# M8650D_eco.net
KiCad netlist of a schematic drawn in EAGLE
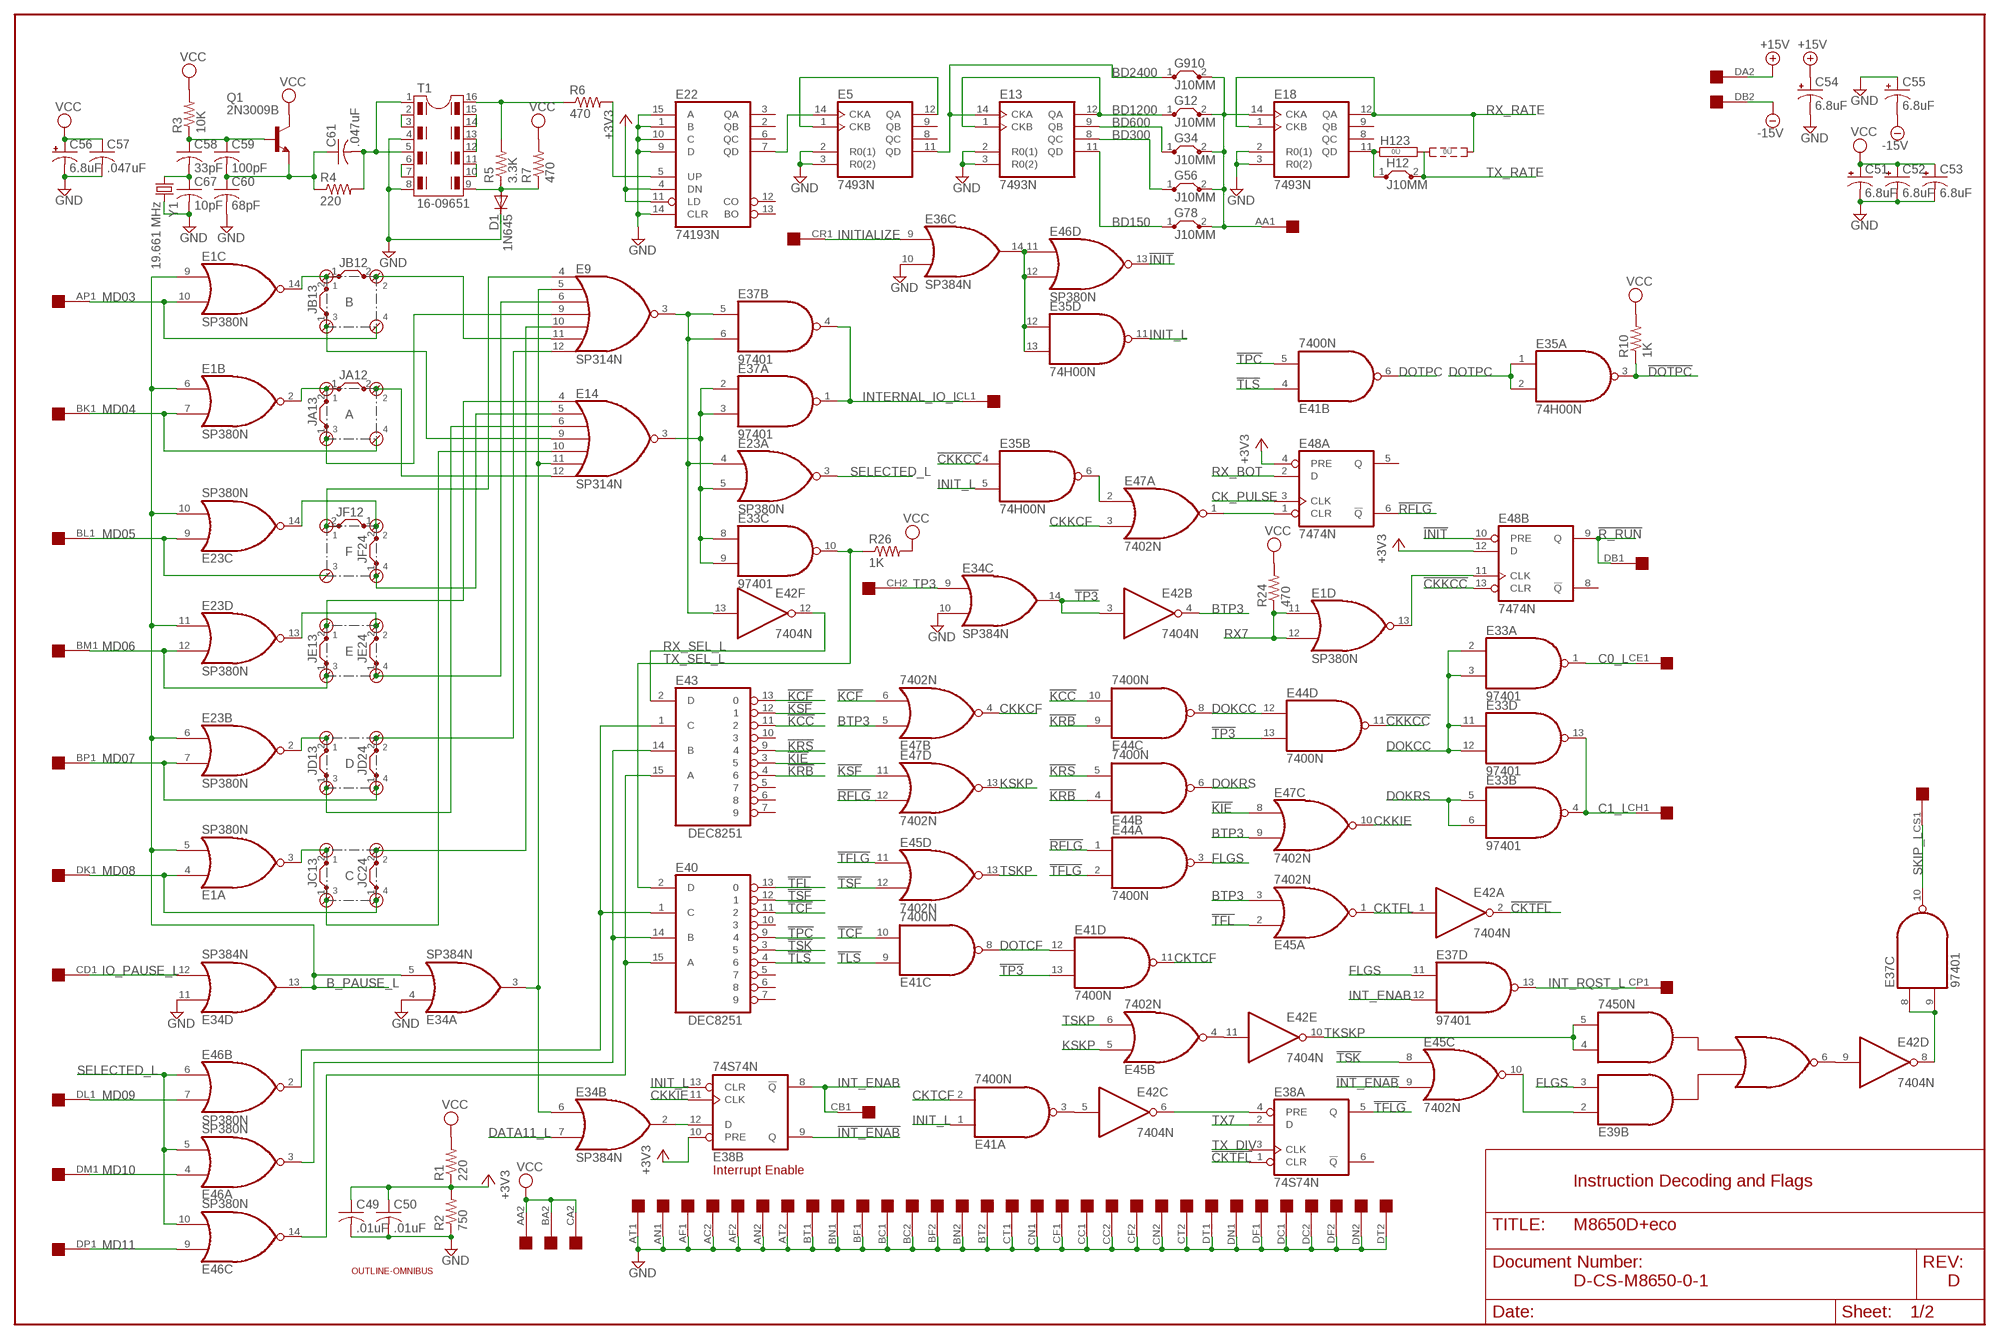
[diagram p0: schematic, sheet 1]
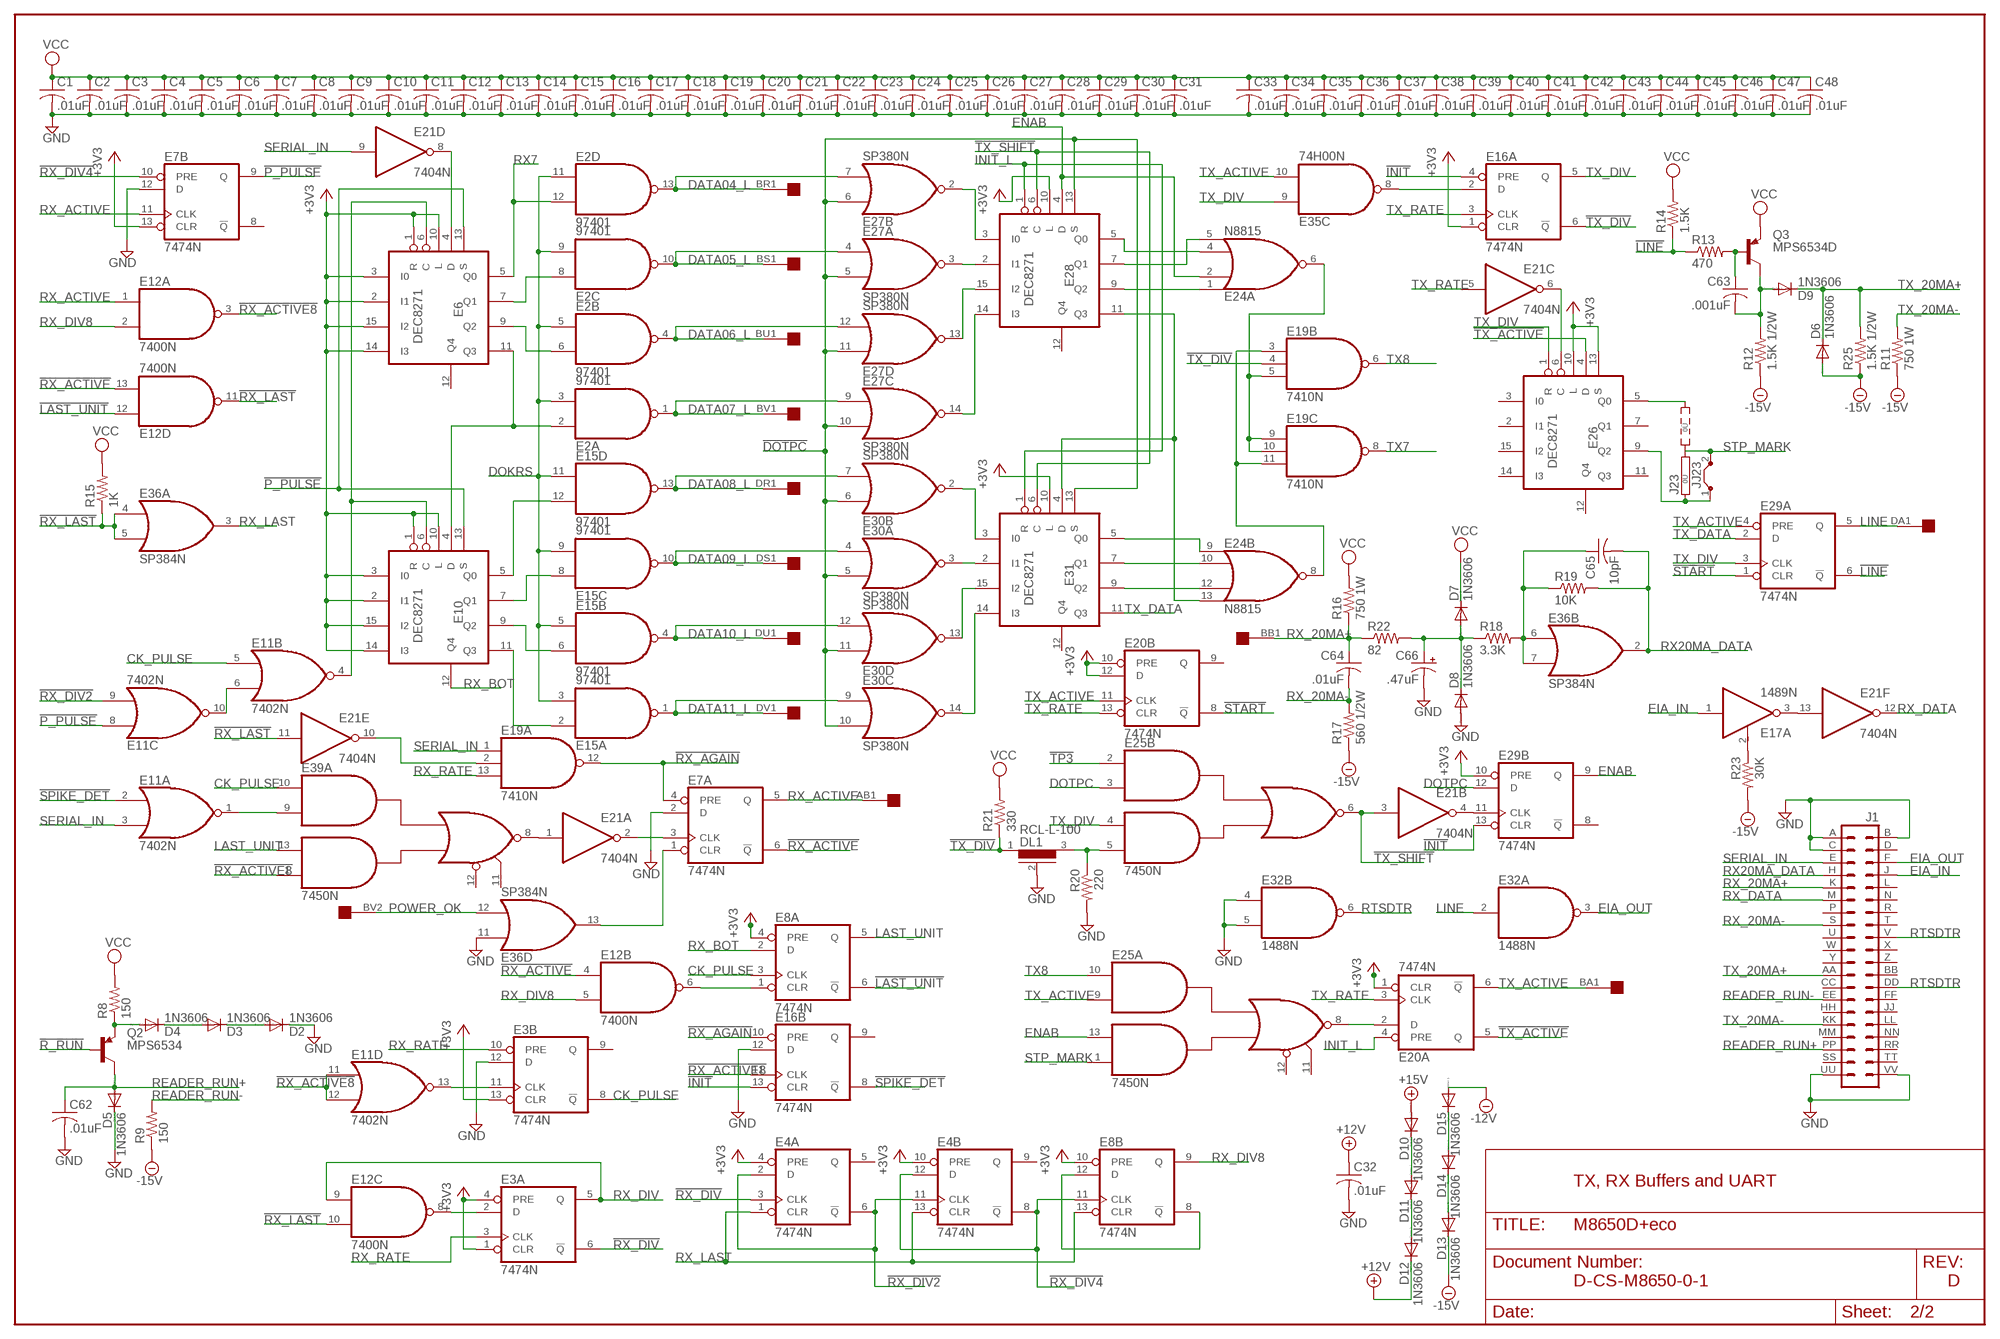
[diagram p1: schematic, sheet 2]

(export (version "E")
  (design (tool "Eeschema 10.0.6"))
  (components
    (comp (ref "A")
      (value "JUMPER4")
      (footprint "eagle-import:JUMPER4")
      (libsource (lib "eagle-import") (part "JUMPER4"))
    )
    (comp (ref "B")
      (value "JUMPER4")
      (footprint "eagle-import:JUMPER4")
      (libsource (lib "eagle-import") (part "JUMPER4"))
    )
    (comp (ref "C")
      (value "JUMPER4")
      (footprint "eagle-import:JUMPER4")
      (libsource (lib "eagle-import") (part "JUMPER4"))
    )
    (comp (ref "C49")
      (value ".01uF")
      (footprint "eagle-import:C050-025X075")
      (libsource (lib "eagle-import") (part "C-US050-025X075"))
    )
    (comp (ref "C50")
      (value ".01uF")
      (footprint "eagle-import:C050-025X075")
      (libsource (lib "eagle-import") (part "C-US050-025X075"))
    )
    (comp (ref "C51")
      (value "6.8uF")
      (footprint "eagle-import:E12-8")
      (libsource (lib "eagle-import") (part "CPOL-USE20-8AXIAL"))
    )
    (comp (ref "C52")
      (value "6.8uF")
      (footprint "eagle-import:E12-8")
      (libsource (lib "eagle-import") (part "CPOL-USE20-8AXIAL"))
    )
    (comp (ref "C53")
      (value "6.8uF")
      (footprint "eagle-import:E12-8")
      (libsource (lib "eagle-import") (part "CPOL-USE20-8AXIAL"))
    )
    (comp (ref "C54")
      (value "6.8uF")
      (footprint "eagle-import:E12-8")
      (libsource (lib "eagle-import") (part "CPOL-USE20-8AXIAL"))
    )
    (comp (ref "C55")
      (value "6.8uF")
      (footprint "eagle-import:E12-8")
      (libsource (lib "eagle-import") (part "CPOL-USE20-8AXIAL"))
    )
    (comp (ref "C56")
      (value "6.8uF")
      (footprint "eagle-import:E12-8")
      (libsource (lib "eagle-import") (part "CPOL-USE20-8AXIAL"))
    )
    (comp (ref "C57")
      (value ".047uF")
      (footprint "eagle-import:C050-025X075")
      (libsource (lib "eagle-import") (part "C-US050-025X075"))
    )
    (comp (ref "C58")
      (value "33pF")
      (footprint "eagle-import:C050-025X075")
      (libsource (lib "eagle-import") (part "C-US050-025X075"))
    )
    (comp (ref "C59")
      (value "100pF")
      (footprint "eagle-import:C050-025X075")
      (libsource (lib "eagle-import") (part "C-US050-025X075"))
    )
    (comp (ref "C60")
      (value "68pF")
      (footprint "eagle-import:C050-025X075")
      (libsource (lib "eagle-import") (part "C-US050-025X075"))
    )
    (comp (ref "C61")
      (value ".047uF")
      (footprint "eagle-import:C050-025X075")
      (libsource (lib "eagle-import") (part "C-US050-025X075"))
    )
    (comp (ref "C67")
      (value "10pF")
      (footprint "eagle-import:C050-025X075")
      (libsource (lib "eagle-import") (part "C-US050-025X075"))
    )
    (comp (ref "D")
      (value "JUMPER4")
      (footprint "eagle-import:JUMPER4")
      (libsource (lib "eagle-import") (part "JUMPER4"))
    )
    (comp (ref "D1")
      (value "1N645")
      (footprint "eagle-import:DO35-10")
      (libsource (lib "eagle-import") (part "DIODE-DO35-10"))
    )
    (comp (ref "E")
      (value "JUMPER4")
      (footprint "eagle-import:JUMPER4")
      (libsource (lib "eagle-import") (part "JUMPER4"))
    )
    (comp (ref "E1")
      (value "SP380N")
      (footprint "eagle-import:DIL14")
      (libsource (lib "eagle-import") (part "SP380N"))
    )
    (comp (ref "E5")
      (value "7493N")
      (footprint "eagle-import:DIL14")
      (libsource (lib "eagle-import") (part "7493NLS"))
    )
    (comp (ref "E9")
      (value "SP314N")
      (footprint "eagle-import:DIL14")
      (libsource (lib "eagle-import") (part "SP314N"))
    )
    (comp (ref "E13")
      (value "7493N")
      (footprint "eagle-import:DIL14")
      (libsource (lib "eagle-import") (part "7493NLS"))
    )
    (comp (ref "E14")
      (value "SP314N")
      (footprint "eagle-import:DIL14")
      (libsource (lib "eagle-import") (part "SP314N"))
    )
    (comp (ref "E18")
      (value "7493N")
      (footprint "eagle-import:DIL14")
      (libsource (lib "eagle-import") (part "7493NLS"))
    )
    (comp (ref "E22")
      (value "74193N")
      (footprint "eagle-import:DIL16")
      (libsource (lib "eagle-import") (part "74193N"))
    )
    (comp (ref "E23")
      (value "SP380N")
      (footprint "eagle-import:DIL14")
      (libsource (lib "eagle-import") (part "SP380N"))
    )
    (comp (ref "E33")
      (value "97401")
      (footprint "eagle-import:DIL14")
      (libsource (lib "eagle-import") (part "7401NLS"))
    )
    (comp (ref "E34")
      (value "SP384N")
      (footprint "eagle-import:DIL14")
      (libsource (lib "eagle-import") (part "SP384N"))
    )
    (comp (ref "E35")
      (value "74H00N")
      (footprint "eagle-import:DIL14")
      (libsource (lib "eagle-import") (part "7400N"))
    )
    (comp (ref "E36")
      (value "SP384N")
      (footprint "eagle-import:DIL14")
      (libsource (lib "eagle-import") (part "SP384N"))
    )
    (comp (ref "E37")
      (value "97401")
      (footprint "eagle-import:DIL14")
      (libsource (lib "eagle-import") (part "7401NLS"))
    )
    (comp (ref "E38")
      (value "74S74N")
      (footprint "eagle-import:DIL14")
      (libsource (lib "eagle-import") (part "7474NS"))
    )
    (comp (ref "E39")
      (value "7450N")
      (footprint "eagle-import:DIL14")
      (libsource (lib "eagle-import") (part "7450N"))
    )
    (comp (ref "E40")
      (value "DEC8251")
      (footprint "eagle-import:DIL16")
      (libsource (lib "eagle-import") (part "DEC8251"))
    )
    (comp (ref "E41")
      (value "7400N")
      (footprint "eagle-import:DIL14")
      (libsource (lib "eagle-import") (part "7400N"))
    )
    (comp (ref "E42")
      (value "7404N")
      (footprint "eagle-import:DIL14")
      (libsource (lib "eagle-import") (part "7404N"))
    )
    (comp (ref "E43")
      (value "DEC8251")
      (footprint "eagle-import:DIL16")
      (libsource (lib "eagle-import") (part "DEC8251"))
    )
    (comp (ref "E44")
      (value "7400N")
      (footprint "eagle-import:DIL14")
      (libsource (lib "eagle-import") (part "7400N"))
    )
    (comp (ref "E45")
      (value "7402N")
      (footprint "eagle-import:DIL14")
      (libsource (lib "eagle-import") (part "7402N"))
    )
    (comp (ref "E46")
      (value "SP380N")
      (footprint "eagle-import:DIL14")
      (libsource (lib "eagle-import") (part "SP380N"))
    )
    (comp (ref "E47")
      (value "7402N")
      (footprint "eagle-import:DIL14")
      (libsource (lib "eagle-import") (part "7402N"))
    )
    (comp (ref "E48")
      (value "7474N")
      (footprint "eagle-import:DIL14")
      (libsource (lib "eagle-import") (part "7474NS"))
    )
    (comp (ref "F")
      (value "JUMPER4")
      (footprint "eagle-import:JUMPER4")
      (libsource (lib "eagle-import") (part "JUMPER4"))
    )
    (comp (ref "G12")
      (value "J10MM")
      (footprint "eagle-import:10")
      (libsource (lib "eagle-import") (part "J10MM"))
    )
    (comp (ref "G34")
      (value "J10MM")
      (footprint "eagle-import:10")
      (libsource (lib "eagle-import") (part "J10MM"))
    )
    (comp (ref "G56")
      (value "J10MM")
      (footprint "eagle-import:10")
      (libsource (lib "eagle-import") (part "J10MM"))
    )
    (comp (ref "G78")
      (value "J10MM")
      (footprint "eagle-import:10")
      (libsource (lib "eagle-import") (part "J10MM"))
    )
    (comp (ref "G910")
      (value "J10MM")
      (footprint "eagle-import:10")
      (libsource (lib "eagle-import") (part "J10MM"))
    )
    (comp (ref "H12")
      (value "J10MM")
      (footprint "eagle-import:10")
      (libsource (lib "eagle-import") (part "J10MM"))
    )
    (comp (ref "H123")
      (value "0R2")
      (footprint "eagle-import:0R2_10")
      (libsource (lib "eagle-import") (part "0R2"))
    )
    (comp (ref "JA12")
      (value "J10MM")
      (footprint "eagle-import:10")
      (libsource (lib "eagle-import") (part "J10MM"))
    )
    (comp (ref "JA13")
      (value "J10MM")
      (footprint "eagle-import:10")
      (libsource (lib "eagle-import") (part "J10MM"))
    )
    (comp (ref "JB12")
      (value "J10MM")
      (footprint "eagle-import:10")
      (libsource (lib "eagle-import") (part "J10MM"))
    )
    (comp (ref "JB13")
      (value "J10MM")
      (footprint "eagle-import:10")
      (libsource (lib "eagle-import") (part "J10MM"))
    )
    (comp (ref "JC13")
      (value "J10MM")
      (footprint "eagle-import:10")
      (libsource (lib "eagle-import") (part "J10MM"))
    )
    (comp (ref "JC24")
      (value "J10MM")
      (footprint "eagle-import:10")
      (libsource (lib "eagle-import") (part "J10MM"))
    )
    (comp (ref "JD13")
      (value "J10MM")
      (footprint "eagle-import:10")
      (libsource (lib "eagle-import") (part "J10MM"))
    )
    (comp (ref "JD24")
      (value "J10MM")
      (footprint "eagle-import:10")
      (libsource (lib "eagle-import") (part "J10MM"))
    )
    (comp (ref "JE13")
      (value "J10MM")
      (footprint "eagle-import:10")
      (libsource (lib "eagle-import") (part "J10MM"))
    )
    (comp (ref "JE24")
      (value "J10MM")
      (footprint "eagle-import:10")
      (libsource (lib "eagle-import") (part "J10MM"))
    )
    (comp (ref "JF12")
      (value "J10MM")
      (footprint "eagle-import:10")
      (libsource (lib "eagle-import") (part "J10MM"))
    )
    (comp (ref "JF24")
      (value "J10MM")
      (footprint "eagle-import:10")
      (libsource (lib "eagle-import") (part "J10MM"))
    )
    (comp (ref "Q1")
      (value "2N3009B")
      (footprint "eagle-import:TO5")
      (libsource (lib "eagle-import") (part "-NPN-TO5"))
    )
    (comp (ref "R1")
      (value "220")
      (footprint "eagle-import:0207_10")
      (libsource (lib "eagle-import") (part "R-US_0207/10"))
    )
    (comp (ref "R2")
      (value "750")
      (footprint "eagle-import:0207_10")
      (libsource (lib "eagle-import") (part "R-US_0207/10"))
    )
    (comp (ref "R3")
      (value "10K")
      (footprint "eagle-import:0207_10")
      (libsource (lib "eagle-import") (part "R-US_0207/10"))
    )
    (comp (ref "R4")
      (value "220")
      (footprint "eagle-import:0207_10")
      (libsource (lib "eagle-import") (part "R-US_0207/10"))
    )
    (comp (ref "R5")
      (value "3.3K")
      (footprint "eagle-import:0207_10")
      (libsource (lib "eagle-import") (part "R-US_0207/10"))
    )
    (comp (ref "R6")
      (value "470")
      (footprint "eagle-import:0207_10")
      (libsource (lib "eagle-import") (part "R-US_0207/10"))
    )
    (comp (ref "R7")
      (value "470")
      (footprint "eagle-import:0207_10")
      (libsource (lib "eagle-import") (part "R-US_0207/10"))
    )
    (comp (ref "R10")
      (value "1K")
      (footprint "eagle-import:0207_10")
      (libsource (lib "eagle-import") (part "R-US_0207/10"))
    )
    (comp (ref "R24")
      (value "470")
      (footprint "eagle-import:0207_10")
      (libsource (lib "eagle-import") (part "R-US_0207/10"))
    )
    (comp (ref "R26")
      (value "1K")
      (footprint "eagle-import:0207_10")
      (libsource (lib "eagle-import") (part "R-US_0207/10"))
    )
    (comp (ref "T1")
      (value "16-09651")
      (footprint "eagle-import:DIL16")
      (libsource (lib "eagle-import") (part "DIL16"))
    )
    (comp (ref "U$1")
      (value "OUTLINE-OMNIBUS")
      (footprint "eagle-import:OMNIBUS")
      (libsource (lib "eagle-import") (part "OUTLINE-OMNIBUS"))
    )
    (comp (ref "U$2")
      (value "QUAD")
      (footprint "eagle-import:EDGE-CON8")
      (libsource (lib "eagle-import") (part "QUAD"))
    )
    (comp (ref "Y1")
      (value "19.661 MHz")
      (footprint "eagle-import:HC49TL-H")
      (libsource (lib "eagle-import") (part "CRYSTALHC49TL-H"))
    )
    (comp (ref "C1")
      (value ".01uF")
      (footprint "eagle-import:C050-025X075")
      (libsource (lib "eagle-import") (part "C-US050-025X075"))
    )
    (comp (ref "C2")
      (value ".01uF")
      (footprint "eagle-import:C050-025X075")
      (libsource (lib "eagle-import") (part "C-US050-025X075"))
    )
    (comp (ref "C3")
      (value ".01uF")
      (footprint "eagle-import:C050-025X075")
      (libsource (lib "eagle-import") (part "C-US050-025X075"))
    )
    (comp (ref "C4")
      (value ".01uF")
      (footprint "eagle-import:C050-025X075")
      (libsource (lib "eagle-import") (part "C-US050-025X075"))
    )
    (comp (ref "C5")
      (value ".01uF")
      (footprint "eagle-import:C050-025X075")
      (libsource (lib "eagle-import") (part "C-US050-025X075"))
    )
    (comp (ref "C6")
      (value ".01uF")
      (footprint "eagle-import:C050-025X075")
      (libsource (lib "eagle-import") (part "C-US050-025X075"))
    )
    (comp (ref "C7")
      (value ".01uF")
      (footprint "eagle-import:C050-025X075")
      (libsource (lib "eagle-import") (part "C-US050-025X075"))
    )
    (comp (ref "C8")
      (value ".01uF")
      (footprint "eagle-import:C050-025X075")
      (libsource (lib "eagle-import") (part "C-US050-025X075"))
    )
    (comp (ref "C9")
      (value ".01uF")
      (footprint "eagle-import:C050-025X075")
      (libsource (lib "eagle-import") (part "C-US050-025X075"))
    )
    (comp (ref "C10")
      (value ".01uF")
      (footprint "eagle-import:C050-025X075")
      (libsource (lib "eagle-import") (part "C-US050-025X075"))
    )
    (comp (ref "C11")
      (value ".01uF")
      (footprint "eagle-import:C050-025X075")
      (libsource (lib "eagle-import") (part "C-US050-025X075"))
    )
    (comp (ref "C12")
      (value ".01uF")
      (footprint "eagle-import:C050-025X075")
      (libsource (lib "eagle-import") (part "C-US050-025X075"))
    )
    (comp (ref "C13")
      (value ".01uF")
      (footprint "eagle-import:C050-025X075")
      (libsource (lib "eagle-import") (part "C-US050-025X075"))
    )
    (comp (ref "C14")
      (value ".01uF")
      (footprint "eagle-import:C050-025X075")
      (libsource (lib "eagle-import") (part "C-US050-025X075"))
    )
    (comp (ref "C15")
      (value ".01uF")
      (footprint "eagle-import:C050-025X075")
      (libsource (lib "eagle-import") (part "C-US050-025X075"))
    )
    (comp (ref "C16")
      (value ".01uF")
      (footprint "eagle-import:C050-025X075")
      (libsource (lib "eagle-import") (part "C-US050-025X075"))
    )
    (comp (ref "C17")
      (value ".01uF")
      (footprint "eagle-import:C050-025X075")
      (libsource (lib "eagle-import") (part "C-US050-025X075"))
    )
    (comp (ref "C18")
      (value ".01uF")
      (footprint "eagle-import:C050-025X075")
      (libsource (lib "eagle-import") (part "C-US050-025X075"))
    )
    (comp (ref "C19")
      (value ".01uF")
      (footprint "eagle-import:C050-025X075")
      (libsource (lib "eagle-import") (part "C-US050-025X075"))
    )
    (comp (ref "C20")
      (value ".01uF")
      (footprint "eagle-import:C050-025X075")
      (libsource (lib "eagle-import") (part "C-US050-025X075"))
    )
    (comp (ref "C21")
      (value ".01uF")
      (footprint "eagle-import:C050-025X075")
      (libsource (lib "eagle-import") (part "C-US050-025X075"))
    )
    (comp (ref "C22")
      (value ".01uF")
      (footprint "eagle-import:C050-025X075")
      (libsource (lib "eagle-import") (part "C-US050-025X075"))
    )
    (comp (ref "C23")
      (value ".01uF")
      (footprint "eagle-import:C050-025X075")
      (libsource (lib "eagle-import") (part "C-US050-025X075"))
    )
    (comp (ref "C24")
      (value ".01uF")
      (footprint "eagle-import:C050-025X075")
      (libsource (lib "eagle-import") (part "C-US050-025X075"))
    )
    (comp (ref "C25")
      (value ".01uF")
      (footprint "eagle-import:C050-025X075")
      (libsource (lib "eagle-import") (part "C-US050-025X075"))
    )
    (comp (ref "C26")
      (value ".01uF")
      (footprint "eagle-import:C050-025X075")
      (libsource (lib "eagle-import") (part "C-US050-025X075"))
    )
    (comp (ref "C27")
      (value ".01uF")
      (footprint "eagle-import:C050-025X075")
      (libsource (lib "eagle-import") (part "C-US050-025X075"))
    )
    (comp (ref "C28")
      (value ".01uF")
      (footprint "eagle-import:C050-025X075")
      (libsource (lib "eagle-import") (part "C-US050-025X075"))
    )
    (comp (ref "C29")
      (value ".01uF")
      (footprint "eagle-import:C050-025X075")
      (libsource (lib "eagle-import") (part "C-US050-025X075"))
    )
    (comp (ref "C30")
      (value ".01uF")
      (footprint "eagle-import:C050-025X075")
      (libsource (lib "eagle-import") (part "C-US050-025X075"))
    )
    (comp (ref "C31")
      (value ".01uF")
      (footprint "eagle-import:C050-025X075")
      (libsource (lib "eagle-import") (part "C-US050-025X075"))
    )
    (comp (ref "C32")
      (value ".01uF")
      (footprint "eagle-import:C050-025X075")
      (libsource (lib "eagle-import") (part "C-US050-025X075"))
    )
    (comp (ref "C33")
      (value ".01uF")
      (footprint "eagle-import:C050-025X075")
      (libsource (lib "eagle-import") (part "C-US050-025X075"))
    )
    (comp (ref "C34")
      (value ".01uF")
      (footprint "eagle-import:C050-025X075")
      (libsource (lib "eagle-import") (part "C-US050-025X075"))
    )
    (comp (ref "C35")
      (value ".01uF")
      (footprint "eagle-import:C050-025X075")
      (libsource (lib "eagle-import") (part "C-US050-025X075"))
    )
    (comp (ref "C36")
      (value ".01uF")
      (footprint "eagle-import:C050-025X075")
      (libsource (lib "eagle-import") (part "C-US050-025X075"))
    )
    (comp (ref "C37")
      (value ".01uF")
      (footprint "eagle-import:C050-025X075")
      (libsource (lib "eagle-import") (part "C-US050-025X075"))
    )
    (comp (ref "C38")
      (value ".01uF")
      (footprint "eagle-import:C050-025X075")
      (libsource (lib "eagle-import") (part "C-US050-025X075"))
    )
    (comp (ref "C39")
      (value ".01uF")
      (footprint "eagle-import:C050-025X075")
      (libsource (lib "eagle-import") (part "C-US050-025X075"))
    )
    (comp (ref "C40")
      (value ".01uF")
      (footprint "eagle-import:C050-025X075")
      (libsource (lib "eagle-import") (part "C-US050-025X075"))
    )
    (comp (ref "C41")
      (value ".01uF")
      (footprint "eagle-import:C050-025X075")
      (libsource (lib "eagle-import") (part "C-US050-025X075"))
    )
    (comp (ref "C42")
      (value ".01uF")
      (footprint "eagle-import:C050-025X075")
      (libsource (lib "eagle-import") (part "C-US050-025X075"))
    )
    (comp (ref "C43")
      (value ".01uF")
      (footprint "eagle-import:C050-025X075")
      (libsource (lib "eagle-import") (part "C-US050-025X075"))
    )
    (comp (ref "C44")
      (value ".01uF")
      (footprint "eagle-import:C050-025X075")
      (libsource (lib "eagle-import") (part "C-US050-025X075"))
    )
    (comp (ref "C45")
      (value ".01uF")
      (footprint "eagle-import:C050-025X075")
      (libsource (lib "eagle-import") (part "C-US050-025X075"))
    )
    (comp (ref "C46")
      (value ".01uF")
      (footprint "eagle-import:C050-025X075")
      (libsource (lib "eagle-import") (part "C-US050-025X075"))
    )
    (comp (ref "C47")
      (value ".01uF")
      (footprint "eagle-import:C050-025X075")
      (libsource (lib "eagle-import") (part "C-US050-025X075"))
    )
    (comp (ref "C48")
      (value ".01uF")
      (footprint "eagle-import:C050-025X075")
      (libsource (lib "eagle-import") (part "C-US050-025X075"))
    )
    (comp (ref "C62")
      (value ".01uF")
      (footprint "eagle-import:C050-025X075")
      (libsource (lib "eagle-import") (part "C-US050-025X075"))
    )
    (comp (ref "C63")
      (value ".001uF")
      (footprint "eagle-import:C050-025X075")
      (libsource (lib "eagle-import") (part "C-US050-025X075"))
    )
    (comp (ref "C64")
      (value ".01uF")
      (footprint "eagle-import:C050-025X075")
      (libsource (lib "eagle-import") (part "C-US050-025X075"))
    )
    (comp (ref "C65")
      (value "10pF")
      (footprint "eagle-import:C050-025X075")
      (libsource (lib "eagle-import") (part "C-US050-025X075"))
    )
    (comp (ref "C66")
      (value ".47uF")
      (footprint "eagle-import:E15-5")
      (libsource (lib "eagle-import") (part "CPOL-USE15-5AXIAL"))
    )
    (comp (ref "D2")
      (value "1N3606")
      (footprint "eagle-import:DO35-10")
      (libsource (lib "eagle-import") (part "DIODE-DO35-10"))
    )
    (comp (ref "D3")
      (value "1N3606")
      (footprint "eagle-import:DO35-10")
      (libsource (lib "eagle-import") (part "DIODE-DO35-10"))
    )
    (comp (ref "D4")
      (value "1N3606")
      (footprint "eagle-import:DO35-10")
      (libsource (lib "eagle-import") (part "DIODE-DO35-10"))
    )
    (comp (ref "D5")
      (value "1N3606")
      (footprint "eagle-import:DO35-10")
      (libsource (lib "eagle-import") (part "DIODE-DO35-10"))
    )
    (comp (ref "D6")
      (value "1N3606")
      (footprint "eagle-import:DO35-10")
      (libsource (lib "eagle-import") (part "DIODE-DO35-10"))
    )
    (comp (ref "D7")
      (value "1N3606")
      (footprint "eagle-import:DO35-10")
      (libsource (lib "eagle-import") (part "DIODE-DO35-10"))
    )
    (comp (ref "D8")
      (value "1N3606")
      (footprint "eagle-import:DO35-10")
      (libsource (lib "eagle-import") (part "DIODE-DO35-10"))
    )
    (comp (ref "D9")
      (value "1N3606")
      (footprint "eagle-import:DO35-10")
      (libsource (lib "eagle-import") (part "DIODE-DO35-10"))
    )
    (comp (ref "D10")
      (value "1N3606")
      (footprint "eagle-import:DO35-10")
      (libsource (lib "eagle-import") (part "DIODE-DO35-10"))
    )
    (comp (ref "D11")
      (value "1N3606")
      (footprint "eagle-import:DO35-10")
      (libsource (lib "eagle-import") (part "DIODE-DO35-10"))
    )
    (comp (ref "D12")
      (value "1N3606")
      (footprint "eagle-import:DO35-10")
      (libsource (lib "eagle-import") (part "DIODE-DO35-10"))
    )
    (comp (ref "D13")
      (value "1N3606")
      (footprint "eagle-import:DO35-10")
      (libsource (lib "eagle-import") (part "DIODE-DO35-10"))
    )
    (comp (ref "D14")
      (value "1N3606")
      (footprint "eagle-import:DO35-10")
      (libsource (lib "eagle-import") (part "DIODE-DO35-10"))
    )
    (comp (ref "D15")
      (value "1N3606")
      (footprint "eagle-import:DO35-10")
      (libsource (lib "eagle-import") (part "DIODE-DO35-10"))
    )
    (comp (ref "DL1")
      (value "RCL-L-100")
      (footprint "eagle-import:RCL-L-00-05")
      (libsource (lib "eagle-import") (part "RCL-L-00-05"))
    )
    (comp (ref "E2")
      (value "97401")
      (footprint "eagle-import:DIL14")
      (libsource (lib "eagle-import") (part "7401NLS"))
    )
    (comp (ref "E3")
      (value "7474N")
      (footprint "eagle-import:DIL14")
      (libsource (lib "eagle-import") (part "7474NS"))
    )
    (comp (ref "E4")
      (value "7474N")
      (footprint "eagle-import:DIL14")
      (libsource (lib "eagle-import") (part "7474NS"))
    )
    (comp (ref "E6")
      (value "DEC8271")
      (footprint "eagle-import:DIL16")
      (libsource (lib "eagle-import") (part "DEC8271"))
    )
    (comp (ref "E7")
      (value "7474N")
      (footprint "eagle-import:DIL14")
      (libsource (lib "eagle-import") (part "7474NS"))
    )
    (comp (ref "E8")
      (value "7474N")
      (footprint "eagle-import:DIL14")
      (libsource (lib "eagle-import") (part "7474NS"))
    )
    (comp (ref "E10")
      (value "DEC8271")
      (footprint "eagle-import:DIL16")
      (libsource (lib "eagle-import") (part "DEC8271"))
    )
    (comp (ref "E11")
      (value "7402N")
      (footprint "eagle-import:DIL14")
      (libsource (lib "eagle-import") (part "7402N"))
    )
    (comp (ref "E12")
      (value "7400N")
      (footprint "eagle-import:DIL14")
      (libsource (lib "eagle-import") (part "7400N"))
    )
    (comp (ref "E15")
      (value "97401")
      (footprint "eagle-import:DIL14")
      (libsource (lib "eagle-import") (part "7401NLS"))
    )
    (comp (ref "E16")
      (value "7474N")
      (footprint "eagle-import:DIL14")
      (libsource (lib "eagle-import") (part "7474NS"))
    )
    (comp (ref "E17")
      (value "1489N")
      (footprint "eagle-import:DIL14")
      (libsource (lib "eagle-import") (part "1489N"))
    )
    (comp (ref "E19")
      (value "7410N")
      (footprint "eagle-import:DIL14")
      (libsource (lib "eagle-import") (part "7410N"))
    )
    (comp (ref "E20")
      (value "7474N")
      (footprint "eagle-import:DIL14")
      (libsource (lib "eagle-import") (part "7474NS"))
    )
    (comp (ref "E21")
      (value "7404N")
      (footprint "eagle-import:DIL14")
      (libsource (lib "eagle-import") (part "7404N"))
    )
    (comp (ref "E24")
      (value "N8815")
      (footprint "eagle-import:DIL14")
      (libsource (lib "eagle-import") (part "N8815"))
    )
    (comp (ref "E25")
      (value "7450N")
      (footprint "eagle-import:DIL14")
      (libsource (lib "eagle-import") (part "7450N"))
    )
    (comp (ref "E26")
      (value "DEC8271")
      (footprint "eagle-import:DIL16")
      (libsource (lib "eagle-import") (part "DEC8271"))
    )
    (comp (ref "E27")
      (value "SP380N")
      (footprint "eagle-import:DIL14")
      (libsource (lib "eagle-import") (part "SP380N"))
    )
    (comp (ref "E28")
      (value "DEC8271")
      (footprint "eagle-import:DIL16")
      (libsource (lib "eagle-import") (part "DEC8271"))
    )
    (comp (ref "E29")
      (value "7474N")
      (footprint "eagle-import:DIL14")
      (libsource (lib "eagle-import") (part "7474NS"))
    )
    (comp (ref "E30")
      (value "SP380N")
      (footprint "eagle-import:DIL14")
      (libsource (lib "eagle-import") (part "SP380N"))
    )
    (comp (ref "E31")
      (value "DEC8271")
      (footprint "eagle-import:DIL16")
      (libsource (lib "eagle-import") (part "DEC8271"))
    )
    (comp (ref "E32")
      (value "1488N")
      (footprint "eagle-import:DIL14")
      (libsource (lib "eagle-import") (part "1488N"))
    )
    (comp (ref "J1")
      (value "DEC40PINH")
      (footprint "eagle-import:DEC40PINH")
      (libsource (lib "eagle-import") (part "DEC40PINH"))
    )
    (comp (ref "J23")
      (value "0R2")
      (footprint "eagle-import:0R2_10")
      (libsource (lib "eagle-import") (part "0R2"))
    )
    (comp (ref "JJ23")
      (value "J10MM")
      (footprint "eagle-import:10")
      (libsource (lib "eagle-import") (part "J10MM"))
    )
    (comp (ref "Q2")
      (value "MPS6534")
      (footprint "eagle-import:TO5")
      (libsource (lib "eagle-import") (part "-PNP-TO5"))
    )
    (comp (ref "Q3")
      (value "MPS6534D")
      (footprint "eagle-import:TO5")
      (libsource (lib "eagle-import") (part "-PNP-TO5"))
    )
    (comp (ref "R8")
      (value "150")
      (footprint "eagle-import:0207_10")
      (libsource (lib "eagle-import") (part "R-US_0207/10"))
    )
    (comp (ref "R9")
      (value "150")
      (footprint "eagle-import:0207_10")
      (libsource (lib "eagle-import") (part "R-US_0207/10"))
    )
    (comp (ref "R11")
      (value "750 1W")
      (footprint "eagle-import:0617_17")
      (libsource (lib "eagle-import") (part "R-US_0617/17"))
    )
    (comp (ref "R12")
      (value "1.5K 1/2W")
      (footprint "eagle-import:0411_15")
      (libsource (lib "eagle-import") (part "R-US_0411/15"))
    )
    (comp (ref "R13")
      (value "470")
      (footprint "eagle-import:0207_10")
      (libsource (lib "eagle-import") (part "R-US_0207/10"))
    )
    (comp (ref "R14")
      (value "1.5K")
      (footprint "eagle-import:0207_10")
      (libsource (lib "eagle-import") (part "R-US_0207/10"))
    )
    (comp (ref "R15")
      (value "1K")
      (footprint "eagle-import:0207_10")
      (libsource (lib "eagle-import") (part "R-US_0207/10"))
    )
    (comp (ref "R16")
      (value "750 1W")
      (footprint "eagle-import:0617_17")
      (libsource (lib "eagle-import") (part "R-US_0617/17"))
    )
    (comp (ref "R17")
      (value "560 1/2W")
      (footprint "eagle-import:0411_15")
      (libsource (lib "eagle-import") (part "R-US_0411/15"))
    )
    (comp (ref "R18")
      (value "3.3K")
      (footprint "eagle-import:0207_10")
      (libsource (lib "eagle-import") (part "R-US_0207/10"))
    )
    (comp (ref "R19")
      (value "10K")
      (footprint "eagle-import:0207_10")
      (libsource (lib "eagle-import") (part "R-US_0207/10"))
    )
    (comp (ref "R20")
      (value "220")
      (footprint "eagle-import:0207_10")
      (libsource (lib "eagle-import") (part "R-US_0207/10"))
    )
    (comp (ref "R21")
      (value "330")
      (footprint "eagle-import:0207_10")
      (libsource (lib "eagle-import") (part "R-US_0207/10"))
    )
    (comp (ref "R22")
      (value "82")
      (footprint "eagle-import:0207_10")
      (libsource (lib "eagle-import") (part "R-US_0207/10"))
    )
    (comp (ref "R23")
      (value "30K")
      (footprint "eagle-import:0207_10")
      (libsource (lib "eagle-import") (part "R-US_0207/10"))
    )
    (comp (ref "R25")
      (value "1.5K 1/2W")
      (footprint "eagle-import:0411_15")
      (libsource (lib "eagle-import") (part "R-US_0411/15"))
    )
  )
  (nets
    (net (code "1") (name "+3V3") (class "Default")
      (node (ref "C49") (pin "1") (pinfunction "1_1") (pintype "passive"))
      (node (ref "C50") (pin "1") (pinfunction "1_1") (pintype "passive"))
      (node (ref "E10") (pin "1") (pinfunction "R_1") (pintype "input"))
      (node (ref "E10") (pin "10") (pinfunction "L_10") (pintype "input"))
      (node (ref "E10") (pin "14") (pinfunction "I3_14") (pintype "input"))
      (node (ref "E10") (pin "15") (pinfunction "I2_15") (pintype "input"))
      (node (ref "E10") (pin "2") (pinfunction "I1_2") (pintype "input"))
      (node (ref "E10") (pin "3") (pinfunction "I0_3") (pintype "input"))
      (node (ref "E16") (pin "1") (pinfunction "CLR_1") (pintype "input"))
      (node (ref "E20") (pin "1") (pinfunction "CLR_1") (pintype "input"))
      (node (ref "E20") (pin "10") (pinfunction "PRE_10") (pintype "input"))
      (node (ref "E20") (pin "12") (pinfunction "D_12") (pintype "input"))
      (node (ref "E22") (pin "11") (pinfunction "LD_11") (pintype "input"))
      (node (ref "E22") (pin "4") (pinfunction "DN_4") (pintype "input"))
      (node (ref "E26") (pin "10") (pinfunction "L_10") (pintype "input"))
      (node (ref "E26") (pin "13") (pinfunction "S_13") (pintype "input"))
      (node (ref "E28") (pin "10") (pinfunction "L_10") (pintype "input"))
      (node (ref "E29") (pin "10") (pinfunction "PRE_10") (pintype "input"))
      (node (ref "E3") (pin "1") (pinfunction "CLR_1") (pintype "input"))
      (node (ref "E3") (pin "13") (pinfunction "CLR_13") (pintype "input"))
      (node (ref "E3") (pin "4") (pinfunction "PRE_4") (pintype "input"))
      (node (ref "E31") (pin "10") (pinfunction "L_10") (pintype "input"))
      (node (ref "E38") (pin "10") (pinfunction "PRE_10") (pintype "input"))
      (node (ref "E4") (pin "10") (pinfunction "PRE_10") (pintype "input"))
      (node (ref "E4") (pin "4") (pinfunction "PRE_4") (pintype "input"))
      (node (ref "E48") (pin "12") (pinfunction "D_12") (pintype "input"))
      (node (ref "E48") (pin "4") (pinfunction "PRE_4") (pintype "input"))
      (node (ref "E6") (pin "1") (pinfunction "R_1") (pintype "input"))
      (node (ref "E6") (pin "10") (pinfunction "L_10") (pintype "input"))
      (node (ref "E6") (pin "14") (pinfunction "I3_14") (pintype "input"))
      (node (ref "E6") (pin "15") (pinfunction "I2_15") (pintype "input"))
      (node (ref "E6") (pin "2") (pinfunction "I1_2") (pintype "input"))
      (node (ref "E6") (pin "3") (pinfunction "I0_3") (pintype "input"))
      (node (ref "E7") (pin "13") (pinfunction "CLR_13") (pintype "input"))
      (node (ref "E8") (pin "10") (pinfunction "PRE_10") (pintype "input"))
      (node (ref "E8") (pin "4") (pinfunction "PRE_4") (pintype "input"))
      (node (ref "R1") (pin "1") (pinfunction "1_1") (pintype "passive"))
      (node (ref "R2") (pin "2") (pinfunction "2_2") (pintype "passive"))
    )
    (net (code "2") (name "+12V") (class "Default")
      (node (ref "C32") (pin "1") (pinfunction "1_1") (pintype "passive"))
      (node (ref "D12") (pin "C") (pinfunction "C_C") (pintype "passive"))
    )
    (net (code "3") (name "+15V") (class "Default")
      (node (ref "C54") (pin "+") (pinfunction "+_+") (pintype "passive"))
      (node (ref "D10") (pin "A") (pinfunction "A_A") (pintype "passive"))
      (node (ref "U$2") (pin "DA2") (pinfunction "1_DA2") (pintype "bidirectional"))
    )
    (net (code "4") (name "-12V") (class "Default")
      (node (ref "D15") (pin "A") (pinfunction "A_A") (pintype "passive"))
    )
    (net (code "5") (name "-15V") (class "Default")
      (node (ref "C55") (pin "-") (pinfunction "-_-") (pintype "passive"))
      (node (ref "D13") (pin "C") (pinfunction "C_C") (pintype "passive"))
      (node (ref "D6") (pin "A") (pinfunction "A_A") (pintype "passive"))
      (node (ref "R11") (pin "1") (pinfunction "1_1") (pintype "passive"))
      (node (ref "R12") (pin "1") (pinfunction "1_1") (pintype "passive"))
      (node (ref "R17") (pin "1") (pinfunction "1_1") (pintype "passive"))
      (node (ref "R23") (pin "2") (pinfunction "2_2") (pintype "passive"))
      (node (ref "R25") (pin "1") (pinfunction "1_1") (pintype "passive"))
      (node (ref "R9") (pin "1") (pinfunction "1_1") (pintype "passive"))
      (node (ref "U$2") (pin "DB2") (pinfunction "1_DB2") (pintype "bidirectional"))
    )
    (net (code "6") (name "BD150") (class "Default")
      (node (ref "E13") (pin "11") (pinfunction "QD_11") (pintype "output"))
      (node (ref "G78") (pin "1") (pinfunction "1_1") (pintype "passive"))
    )
    (net (code "7") (name "BD300") (class "Default")
      (node (ref "E13") (pin "8") (pinfunction "QC_8") (pintype "output"))
      (node (ref "G56") (pin "1") (pinfunction "1_1") (pintype "passive"))
    )
    (net (code "8") (name "BD600") (class "Default")
      (node (ref "E13") (pin "9") (pinfunction "QB_9") (pintype "output"))
      (node (ref "G34") (pin "1") (pinfunction "1_1") (pintype "passive"))
    )
    (net (code "9") (name "BD1200") (class "Default")
      (node (ref "E13") (pin "1") (pinfunction "CKB_1") (pintype "input"))
      (node (ref "E13") (pin "12") (pinfunction "QA_12") (pintype "output"))
      (node (ref "G12") (pin "1") (pinfunction "1_1") (pintype "passive"))
    )
    (net (code "10") (name "BD2400") (class "Default")
      (node (ref "E13") (pin "14") (pinfunction "CKA_14") (pintype "input"))
      (node (ref "E5") (pin "11") (pinfunction "QD_11") (pintype "output"))
      (node (ref "G910") (pin "1") (pinfunction "1_1") (pintype "passive"))
    )
    (net (code "11") (name "BTP3") (class "Default")
      (node (ref "E42") (pin "4") (pinfunction "O_4") (pintype "output"))
      (node (ref "E45") (pin "3") (pinfunction "I1_3") (pintype "input"))
      (node (ref "E47") (pin "5") (pinfunction "I0_5") (pintype "input"))
      (node (ref "E47") (pin "9") (pinfunction "I1_9") (pintype "input"))
    )
    (net (code "12") (name "B_PAUSE_L") (class "Default")
      (node (ref "E1") (pin "5") (pinfunction "I1_5") (pintype "input"))
      (node (ref "E1") (pin "6") (pinfunction "I0_6") (pintype "input"))
      (node (ref "E1") (pin "9") (pinfunction "I0_9") (pintype "input"))
      (node (ref "E23") (pin "10") (pinfunction "I1_10") (pintype "input"))
      (node (ref "E23") (pin "11") (pinfunction "I0_11") (pintype "input"))
      (node (ref "E23") (pin "6") (pinfunction "I0_6") (pintype "input"))
      (node (ref "E34") (pin "13") (pinfunction "O_13") (pintype "output"))
      (node (ref "E34") (pin "5") (pinfunction "I1_5") (pintype "input"))
    )
    (net (code "13") (name "C0_L") (class "Default")
      (node (ref "E33") (pin "1") (pinfunction "O_1") (pintype "open_collector"))
      (node (ref "U$2") (pin "CE1") (pinfunction "1_CE1") (pintype "bidirectional"))
    )
    (net (code "14") (name "C1_L") (class "Default")
      (node (ref "E33") (pin "13") (pinfunction "O_13") (pintype "open_collector"))
      (node (ref "E33") (pin "4") (pinfunction "O_4") (pintype "open_collector"))
      (node (ref "U$2") (pin "CH1") (pinfunction "1_CH1") (pintype "bidirectional"))
    )
    (net (code "15") (name "CKKCF") (class "Default")
      (node (ref "E47") (pin "3") (pinfunction "I1_3") (pintype "input"))
      (node (ref "E47") (pin "4") (pinfunction "O_4") (pintype "output"))
    )
    (net (code "16") (name "CKKIE") (class "Default")
      (node (ref "E38") (pin "11") (pinfunction "CLK_11") (pintype "input"))
      (node (ref "E47") (pin "10") (pinfunction "O_10") (pintype "output"))
    )
    (net (code "17") (name "CKTCF") (class "Default")
      (node (ref "E41") (pin "11") (pinfunction "O_11") (pintype "output"))
      (node (ref "E41") (pin "2") (pinfunction "I1_2") (pintype "input"))
    )
    (net (code "18") (name "CKTFL") (class "Default")
      (node (ref "E42") (pin "1") (pinfunction "I_1") (pintype "input"))
      (node (ref "E45") (pin "1") (pinfunction "O_1") (pintype "output"))
    )
    (net (code "19") (name "CK_PULSE") (class "Default")
      (node (ref "E11") (pin "5") (pinfunction "I0_5") (pintype "input"))
      (node (ref "E3") (pin "8") (pinfunction "~{Q}_8") (pintype "output"))
      (node (ref "E39") (pin "10") (pinfunction "I1_10") (pintype "input"))
      (node (ref "E48") (pin "3") (pinfunction "CLK_3") (pintype "input"))
      (node (ref "E8") (pin "3") (pinfunction "CLK_3") (pintype "input"))
    )
    (net (code "20") (name "DATA04_L") (class "Default")
      (node (ref "E2") (pin "13") (pinfunction "O_13") (pintype "open_collector"))
      (node (ref "E27") (pin "7") (pinfunction "I1_7") (pintype "input"))
      (node (ref "U$2") (pin "BR1") (pinfunction "1_BR1") (pintype "bidirectional"))
    )
    (net (code "21") (name "DATA05_L") (class "Default")
      (node (ref "E2") (pin "10") (pinfunction "O_10") (pintype "open_collector"))
      (node (ref "E27") (pin "4") (pinfunction "I0_4") (pintype "input"))
      (node (ref "U$2") (pin "BS1") (pinfunction "1_BS1") (pintype "bidirectional"))
    )
    (net (code "22") (name "DATA06_L") (class "Default")
      (node (ref "E2") (pin "4") (pinfunction "O_4") (pintype "open_collector"))
      (node (ref "E27") (pin "12") (pinfunction "I1_12") (pintype "input"))
      (node (ref "U$2") (pin "BU1") (pinfunction "1_BU1") (pintype "bidirectional"))
    )
    (net (code "23") (name "DATA07_L") (class "Default")
      (node (ref "E2") (pin "1") (pinfunction "O_1") (pintype "open_collector"))
      (node (ref "E27") (pin "9") (pinfunction "I0_9") (pintype "input"))
      (node (ref "U$2") (pin "BV1") (pinfunction "1_BV1") (pintype "bidirectional"))
    )
    (net (code "24") (name "DATA08_L") (class "Default")
      (node (ref "E15") (pin "13") (pinfunction "O_13") (pintype "open_collector"))
      (node (ref "E30") (pin "7") (pinfunction "I1_7") (pintype "input"))
      (node (ref "U$2") (pin "DR1") (pinfunction "1_DR1") (pintype "bidirectional"))
    )
    (net (code "25") (name "DATA09_L") (class "Default")
      (node (ref "E15") (pin "10") (pinfunction "O_10") (pintype "open_collector"))
      (node (ref "E30") (pin "4") (pinfunction "I0_4") (pintype "input"))
      (node (ref "U$2") (pin "DS1") (pinfunction "1_DS1") (pintype "bidirectional"))
    )
    (net (code "26") (name "DATA10_L") (class "Default")
      (node (ref "E15") (pin "4") (pinfunction "O_4") (pintype "open_collector"))
      (node (ref "E30") (pin "12") (pinfunction "I1_12") (pintype "input"))
      (node (ref "U$2") (pin "DU1") (pinfunction "1_DU1") (pintype "bidirectional"))
    )
    (net (code "27") (name "DATA11_L") (class "Default")
      (node (ref "E15") (pin "1") (pinfunction "O_1") (pintype "open_collector"))
      (node (ref "E30") (pin "9") (pinfunction "I0_9") (pintype "input"))
      (node (ref "E34") (pin "7") (pinfunction "I1_7") (pintype "input"))
      (node (ref "U$2") (pin "DV1") (pinfunction "1_DV1") (pintype "bidirectional"))
    )
    (net (code "28") (name "DOKCC") (class "Default")
      (node (ref "E33") (pin "11") (pinfunction "I0_11") (pintype "input"))
      (node (ref "E33") (pin "12") (pinfunction "I1_12") (pintype "input"))
      (node (ref "E33") (pin "2") (pinfunction "I0_2") (pintype "input"))
      (node (ref "E33") (pin "3") (pinfunction "I1_3") (pintype "input"))
      (node (ref "E44") (pin "12") (pinfunction "I0_12") (pintype "input"))
      (node (ref "E44") (pin "8") (pinfunction "O_8") (pintype "output"))
    )
    (net (code "29") (name "DOKRS") (class "Default")
      (node (ref "E15") (pin "11") (pinfunction "I0_11") (pintype "input"))
      (node (ref "E15") (pin "3") (pinfunction "I1_3") (pintype "input"))
      (node (ref "E15") (pin "5") (pinfunction "I0_5") (pintype "input"))
      (node (ref "E15") (pin "9") (pinfunction "I1_9") (pintype "input"))
      (node (ref "E2") (pin "11") (pinfunction "I0_11") (pintype "input"))
      (node (ref "E2") (pin "3") (pinfunction "I1_3") (pintype "input"))
      (node (ref "E2") (pin "5") (pinfunction "I0_5") (pintype "input"))
      (node (ref "E2") (pin "9") (pinfunction "I1_9") (pintype "input"))
      (node (ref "E33") (pin "5") (pinfunction "I0_5") (pintype "input"))
      (node (ref "E33") (pin "6") (pinfunction "I1_6") (pintype "input"))
      (node (ref "E44") (pin "6") (pinfunction "O_6") (pintype "output"))
    )
    (net (code "30") (name "DOTCF") (class "Default")
      (node (ref "E41") (pin "12") (pinfunction "I0_12") (pintype "input"))
      (node (ref "E41") (pin "8") (pinfunction "O_8") (pintype "output"))
    )
    (net (code "31") (name "DOTPC") (class "Default")
      (node (ref "E25") (pin "3") (pinfunction "I2_3") (pintype "input"))
      (node (ref "E29") (pin "12") (pinfunction "D_12") (pintype "input"))
      (node (ref "E35") (pin "1") (pinfunction "I0_1") (pintype "input"))
      (node (ref "E35") (pin "2") (pinfunction "I1_2") (pintype "input"))
      (node (ref "E41") (pin "6") (pinfunction "O_6") (pintype "output"))
    )
    (net (code "32") (name "EIA_IN") (class "Default")
      (node (ref "E17") (pin "1") (pinfunction "I_1") (pintype "input"))
      (node (ref "J1") (pin "J") (pinfunction "8_J") (pintype "bidirectional"))
    )
    (net (code "33") (name "EIA_OUT") (class "Default")
      (node (ref "E32") (pin "3") (pinfunction "O_3") (pintype "output"))
      (node (ref "J1") (pin "F") (pinfunction "6_F") (pintype "bidirectional"))
    )
    (net (code "34") (name "ENAB") (class "Default")
      (node (ref "E24") (pin "2") (pinfunction "I1_2") (pintype "input"))
      (node (ref "E25") (pin "13") (pinfunction "I3_13") (pintype "input"))
      (node (ref "E28") (pin "4") (pinfunction "D_4") (pintype "input"))
      (node (ref "E29") (pin "9") (pinfunction "Q_9") (pintype "output"))
    )
    (net (code "35") (name "FLGS") (class "Default")
      (node (ref "E37") (pin "11") (pinfunction "I0_11") (pintype "input"))
      (node (ref "E39") (pin "3") (pinfunction "I2_3") (pintype "input"))
      (node (ref "E44") (pin "3") (pinfunction "O_3") (pintype "output"))
    )
    (net (code "36") (name "GND") (class "Default")
      (node (ref "C1") (pin "2") (pinfunction "2_2") (pintype "passive"))
      (node (ref "C10") (pin "2") (pinfunction "2_2") (pintype "passive"))
      (node (ref "C11") (pin "2") (pinfunction "2_2") (pintype "passive"))
      (node (ref "C12") (pin "2") (pinfunction "2_2") (pintype "passive"))
      (node (ref "C13") (pin "2") (pinfunction "2_2") (pintype "passive"))
      (node (ref "C14") (pin "2") (pinfunction "2_2") (pintype "passive"))
      (node (ref "C15") (pin "2") (pinfunction "2_2") (pintype "passive"))
      (node (ref "C16") (pin "2") (pinfunction "2_2") (pintype "passive"))
      (node (ref "C17") (pin "2") (pinfunction "2_2") (pintype "passive"))
      (node (ref "C18") (pin "2") (pinfunction "2_2") (pintype "passive"))
      (node (ref "C19") (pin "2") (pinfunction "2_2") (pintype "passive"))
      (node (ref "C2") (pin "2") (pinfunction "2_2") (pintype "passive"))
      (node (ref "C20") (pin "2") (pinfunction "2_2") (pintype "passive"))
      (node (ref "C21") (pin "2") (pinfunction "2_2") (pintype "passive"))
      (node (ref "C22") (pin "2") (pinfunction "2_2") (pintype "passive"))
      (node (ref "C23") (pin "2") (pinfunction "2_2") (pintype "passive"))
      (node (ref "C24") (pin "2") (pinfunction "2_2") (pintype "passive"))
      (node (ref "C25") (pin "2") (pinfunction "2_2") (pintype "passive"))
      (node (ref "C26") (pin "2") (pinfunction "2_2") (pintype "passive"))
      (node (ref "C27") (pin "2") (pinfunction "2_2") (pintype "passive"))
      (node (ref "C28") (pin "2") (pinfunction "2_2") (pintype "passive"))
      (node (ref "C29") (pin "2") (pinfunction "2_2") (pintype "passive"))
      (node (ref "C3") (pin "2") (pinfunction "2_2") (pintype "passive"))
      (node (ref "C30") (pin "2") (pinfunction "2_2") (pintype "passive"))
      (node (ref "C31") (pin "2") (pinfunction "2_2") (pintype "passive"))
      (node (ref "C32") (pin "2") (pinfunction "2_2") (pintype "passive"))
      (node (ref "C33") (pin "2") (pinfunction "2_2") (pintype "passive"))
      (node (ref "C34") (pin "2") (pinfunction "2_2") (pintype "passive"))
      (node (ref "C35") (pin "2") (pinfunction "2_2") (pintype "passive"))
      (node (ref "C36") (pin "2") (pinfunction "2_2") (pintype "passive"))
      (node (ref "C37") (pin "2") (pinfunction "2_2") (pintype "passive"))
      (node (ref "C38") (pin "2") (pinfunction "2_2") (pintype "passive"))
      (node (ref "C39") (pin "2") (pinfunction "2_2") (pintype "passive"))
      (node (ref "C4") (pin "2") (pinfunction "2_2") (pintype "passive"))
      (node (ref "C40") (pin "2") (pinfunction "2_2") (pintype "passive"))
      (node (ref "C41") (pin "2") (pinfunction "2_2") (pintype "passive"))
      (node (ref "C42") (pin "2") (pinfunction "2_2") (pintype "passive"))
      (node (ref "C43") (pin "2") (pinfunction "2_2") (pintype "passive"))
      (node (ref "C44") (pin "2") (pinfunction "2_2") (pintype "passive"))
      (node (ref "C45") (pin "2") (pinfunction "2_2") (pintype "passive"))
      (node (ref "C46") (pin "2") (pinfunction "2_2") (pintype "passive"))
      (node (ref "C47") (pin "2") (pinfunction "2_2") (pintype "passive"))
      (node (ref "C48") (pin "2") (pinfunction "2_2") (pintype "passive"))
      (node (ref "C49") (pin "2") (pinfunction "2_2") (pintype "passive"))
      (node (ref "C5") (pin "2") (pinfunction "2_2") (pintype "passive"))
      (node (ref "C50") (pin "2") (pinfunction "2_2") (pintype "passive"))
      (node (ref "C51") (pin "-") (pinfunction "-_-") (pintype "passive"))
      (node (ref "C52") (pin "-") (pinfunction "-_-") (pintype "passive"))
      (node (ref "C53") (pin "-") (pinfunction "-_-") (pintype "passive"))
      (node (ref "C54") (pin "-") (pinfunction "-_-") (pintype "passive"))
      (node (ref "C55") (pin "+") (pinfunction "+_+") (pintype "passive"))
      (node (ref "C56") (pin "-") (pinfunction "-_-") (pintype "passive"))
      (node (ref "C57") (pin "2") (pinfunction "2_2") (pintype "passive"))
      (node (ref "C6") (pin "2") (pinfunction "2_2") (pintype "passive"))
      (node (ref "C60") (pin "2") (pinfunction "2_2") (pintype "passive"))
      (node (ref "C62") (pin "2") (pinfunction "2_2") (pintype "passive"))
      (node (ref "C66") (pin "-") (pinfunction "-_-") (pintype "passive"))
      (node (ref "C67") (pin "2") (pinfunction "2_2") (pintype "passive"))
      (node (ref "C7") (pin "2") (pinfunction "2_2") (pintype "passive"))
      (node (ref "C8") (pin "2") (pinfunction "2_2") (pintype "passive"))
      (node (ref "C9") (pin "2") (pinfunction "2_2") (pintype "passive"))
      (node (ref "D1") (pin "C") (pinfunction "C_C") (pintype "passive"))
      (node (ref "D2") (pin "C") (pinfunction "C_C") (pintype "passive"))
      (node (ref "D5") (pin "C") (pinfunction "C_C") (pintype "passive"))
      (node (ref "D8") (pin "A") (pinfunction "A_A") (pintype "passive"))
      (node (ref "DL1") (pin "2") (pinfunction "2_2") (pintype "passive"))
      (node (ref "E13") (pin "2") (pinfunction "R0(1)_2") (pintype "input"))
      (node (ref "E13") (pin "3") (pinfunction "R0(2)_3") (pintype "input"))
      (node (ref "E16") (pin "12") (pinfunction "D_12") (pintype "input"))
      (node (ref "E18") (pin "2") (pinfunction "R0(1)_2") (pintype "input"))
      (node (ref "E18") (pin "3") (pinfunction "R0(2)_3") (pintype "input"))
      (node (ref "E22") (pin "1") (pinfunction "B_1") (pintype "input"))
      (node (ref "E22") (pin "10") (pinfunction "C_10") (pintype "input"))
      (node (ref "E22") (pin "14") (pinfunction "CLR_14") (pintype "input"))
      (node (ref "E22") (pin "15") (pinfunction "A_15") (pintype "input"))
      (node (ref "E22") (pin "9") (pinfunction "D_9") (pintype "input"))
      (node (ref "E3") (pin "12") (pinfunction "D_12") (pintype "input"))
      (node (ref "E32") (pin "4") (pinfunction "I0_4") (pintype "input"))
      (node (ref "E32") (pin "5") (pinfunction "I1_5") (pintype "input"))
      (node (ref "E34") (pin "10") (pinfunction "I1_10") (pintype "input"))
      (node (ref "E34") (pin "11") (pinfunction "I0_11") (pintype "input"))
      (node (ref "E34") (pin "4") (pinfunction "I0_4") (pintype "input"))
      (node (ref "E36") (pin "10") (pinfunction "I1_10") (pintype "input"))
      (node (ref "E36") (pin "11") (pinfunction "I0_11") (pintype "input"))
      (node (ref "E5") (pin "2") (pinfunction "R0(1)_2") (pintype "input"))
      (node (ref "E5") (pin "3") (pinfunction "R0(2)_3") (pintype "input"))
      (node (ref "E7") (pin "12") (pinfunction "D_12") (pintype "input"))
      (node (ref "E7") (pin "2") (pinfunction "D_2") (pintype "input"))
      (node (ref "J1") (pin "A") (pinfunction "1_A") (pintype "bidirectional"))
      (node (ref "J1") (pin "B") (pinfunction "2_B") (pintype "bidirectional"))
      (node (ref "J1") (pin "C") (pinfunction "3_C") (pintype "bidirectional"))
      (node (ref "J1") (pin "UU") (pinfunction "39_UU") (pintype "bidirectional"))
      (node (ref "J1") (pin "VV") (pinfunction "40_VV") (pintype "bidirectional"))
      (node (ref "R2") (pin "1") (pinfunction "1_1") (pintype "passive"))
      (node (ref "R20") (pin "2") (pinfunction "2_2") (pintype "passive"))
      (node (ref "T1") (pin "4") (pinfunction "4_4") (pintype "passive"))
      (node (ref "T1") (pin "8") (pinfunction "8_8") (pintype "passive"))
      (node (ref "U$2") (pin "AC2") (pinfunction "1_AC2") (pintype "bidirectional"))
      (node (ref "U$2") (pin "AF1") (pinfunction "1_AF1") (pintype "bidirectional"))
      (node (ref "U$2") (pin "AF2") (pinfunction "1_AF2") (pintype "bidirectional"))
      (node (ref "U$2") (pin "AN1") (pinfunction "1_AN1") (pintype "bidirectional"))
      (node (ref "U$2") (pin "AN2") (pinfunction "1_AN2") (pintype "bidirectional"))
      (node (ref "U$2") (pin "AT1") (pinfunction "1_AT1") (pintype "bidirectional"))
      (node (ref "U$2") (pin "AT2") (pinfunction "1_AT2") (pintype "bidirectional"))
      (node (ref "U$2") (pin "BC1") (pinfunction "1_BC1") (pintype "bidirectional"))
      (node (ref "U$2") (pin "BC2") (pinfunction "1_BC2") (pintype "bidirectional"))
      (node (ref "U$2") (pin "BF1") (pinfunction "1_BF1") (pintype "bidirectional"))
      (node (ref "U$2") (pin "BF2") (pinfunction "1_BF2") (pintype "bidirectional"))
      (node (ref "U$2") (pin "BN1") (pinfunction "1_BN1") (pintype "bidirectional"))
      (node (ref "U$2") (pin "BN2") (pinfunction "1_BN2") (pintype "bidirectional"))
      (node (ref "U$2") (pin "BT1") (pinfunction "1_BT1") (pintype "bidirectional"))
      (node (ref "U$2") (pin "BT2") (pinfunction "1_BT2") (pintype "bidirectional"))
      (node (ref "U$2") (pin "CC1") (pinfunction "1_CC1") (pintype "bidirectional"))
      (node (ref "U$2") (pin "CC2") (pinfunction "1_CC2") (pintype "bidirectional"))
      (node (ref "U$2") (pin "CF1") (pinfunction "1_CF1") (pintype "bidirectional"))
      (node (ref "U$2") (pin "CF2") (pinfunction "1_CF2") (pintype "bidirectional"))
      (node (ref "U$2") (pin "CN1") (pinfunction "1_CN1") (pintype "bidirectional"))
      (node (ref "U$2") (pin "CN2") (pinfunction "1_CN2") (pintype "bidirectional"))
      (node (ref "U$2") (pin "CT1") (pinfunction "1_CT1") (pintype "bidirectional"))
      (node (ref "U$2") (pin "CT2") (pinfunction "1_CT2") (pintype "bidirectional"))
      (node (ref "U$2") (pin "DC1") (pinfunction "1_DC1") (pintype "bidirectional"))
      (node (ref "U$2") (pin "DC2") (pinfunction "1_DC2") (pintype "bidirectional"))
      (node (ref "U$2") (pin "DF1") (pinfunction "1_DF1") (pintype "bidirectional"))
      (node (ref "U$2") (pin "DF2") (pinfunction "1_DF2") (pintype "bidirectional"))
      (node (ref "U$2") (pin "DN1") (pinfunction "1_DN1") (pintype "bidirectional"))
      (node (ref "U$2") (pin "DN2") (pinfunction "1_DN2") (pintype "bidirectional"))
      (node (ref "U$2") (pin "DT1") (pinfunction "1_DT1") (pintype "bidirectional"))
      (node (ref "U$2") (pin "DT2") (pinfunction "1_DT2") (pintype "bidirectional"))
      (node (ref "Y1") (pin "2") (pinfunction "2_2") (pintype "passive"))
    )
    (net (code "37") (name "INITIALIZE") (class "Default")
      (node (ref "E36") (pin "9") (pinfunction "I0_9") (pintype "input"))
      (node (ref "U$2") (pin "CR1") (pinfunction "1_CR1") (pintype "bidirectional"))
    )
    (net (code "38") (name "INIT_L") (class "Default")
      (node (ref "E20") (pin "4") (pinfunction "PRE_4") (pintype "input"))
      (node (ref "E28") (pin "1") (pinfunction "R_1") (pintype "input"))
      (node (ref "E31") (pin "1") (pinfunction "R_1") (pintype "input"))
      (node (ref "E35") (pin "11") (pinfunction "O_11") (pintype "output"))
      (node (ref "E35") (pin "5") (pinfunction "I1_5") (pintype "input"))
      (node (ref "E38") (pin "13") (pinfunction "CLR_13") (pintype "input"))
      (node (ref "E41") (pin "1") (pinfunction "I0_1") (pintype "input"))
    )
    (net (code "39") (name "INTERNAL_IO_L") (class "Default")
      (node (ref "E37") (pin "1") (pinfunction "O_1") (pintype "open_collector"))
      (node (ref "E37") (pin "4") (pinfunction "O_4") (pintype "open_collector"))
      (node (ref "U$2") (pin "CL1") (pinfunction "1_CL1") (pintype "bidirectional"))
    )
    (net (code "40") (name "INT_ENAB") (class "Default")
      (node (ref "E37") (pin "12") (pinfunction "I1_12") (pintype "input"))
      (node (ref "E38") (pin "8") (pinfunction "~{Q}_8") (pintype "output"))
      (node (ref "U$2") (pin "CB1") (pinfunction "1_CB1") (pintype "bidirectional"))
    )
    (net (code "41") (name "INT_RQST_L") (class "Default")
      (node (ref "E37") (pin "13") (pinfunction "O_13") (pintype "open_collector"))
      (node (ref "U$2") (pin "CP1") (pinfunction "1_CP1") (pintype "bidirectional"))
    )
    (net (code "42") (name "IO_PAUSE_L") (class "Default")
      (node (ref "E34") (pin "12") (pinfunction "I1_12") (pintype "input"))
      (node (ref "U$2") (pin "CD1") (pinfunction "1_CD1") (pintype "bidirectional"))
    )
    (net (code "43") (name "KSKP") (class "Default")
      (node (ref "E45") (pin "5") (pinfunction "I0_5") (pintype "input"))
      (node (ref "E47") (pin "13") (pinfunction "O_13") (pintype "output"))
    )
    (net (code "44") (name "LAST_UNIT") (class "Default")
      (node (ref "E39") (pin "13") (pinfunction "I3_13") (pintype "input"))
      (node (ref "E8") (pin "5") (pinfunction "Q_5") (pintype "output"))
    )
    (net (code "45") (name "LINE") (class "Default")
      (node (ref "E29") (pin "5") (pinfunction "Q_5") (pintype "output"))
      (node (ref "E32") (pin "2") (pinfunction "I_2") (pintype "input"))
      (node (ref "U$2") (pin "DA1") (pinfunction "1_DA1") (pintype "bidirectional"))
    )
    (net (code "46") (name "MD03") (class "Default")
      (node (ref "B") (pin "4") (pinfunction "4_4") (pintype "passive"))
      (node (ref "E1") (pin "10") (pinfunction "I1_10") (pintype "input"))
      (node (ref "U$2") (pin "AP1") (pinfunction "1_AP1") (pintype "bidirectional"))
    )
    (net (code "47") (name "MD04") (class "Default")
      (node (ref "A") (pin "4") (pinfunction "4_4") (pintype "passive"))
      (node (ref "E1") (pin "7") (pinfunction "I1_7") (pintype "input"))
      (node (ref "U$2") (pin "BK1") (pinfunction "1_BK1") (pintype "bidirectional"))
    )
    (net (code "48") (name "MD05") (class "Default")
      (node (ref "E23") (pin "9") (pinfunction "I0_9") (pintype "input"))
      (node (ref "F") (pin "3") (pinfunction "3_3") (pintype "passive"))
      (node (ref "U$2") (pin "BL1") (pinfunction "1_BL1") (pintype "bidirectional"))
    )
    (net (code "49") (name "MD06") (class "Default")
      (node (ref "E") (pin "3") (pinfunction "3_3") (pintype "passive"))
      (node (ref "E23") (pin "12") (pinfunction "I1_12") (pintype "input"))
      (node (ref "JE13") (pin "1") (pinfunction "1_1") (pintype "passive"))
      (node (ref "U$2") (pin "BM1") (pinfunction "1_BM1") (pintype "bidirectional"))
    )
    (net (code "50") (name "MD07") (class "Default")
      (node (ref "D") (pin "4") (pinfunction "4_4") (pintype "passive"))
      (node (ref "E23") (pin "7") (pinfunction "I1_7") (pintype "input"))
      (node (ref "JD24") (pin "1") (pinfunction "1_1") (pintype "passive"))
      (node (ref "U$2") (pin "BP1") (pinfunction "1_BP1") (pintype "bidirectional"))
    )
    (net (code "51") (name "MD08") (class "Default")
      (node (ref "C") (pin "4") (pinfunction "4_4") (pintype "passive"))
      (node (ref "E1") (pin "4") (pinfunction "I0_4") (pintype "input"))
      (node (ref "JC24") (pin "1") (pinfunction "1_1") (pintype "passive"))
      (node (ref "U$2") (pin "DK1") (pinfunction "1_DK1") (pintype "bidirectional"))
    )
    (net (code "52") (name "MD09") (class "Default")
      (node (ref "E46") (pin "7") (pinfunction "I1_7") (pintype "input"))
      (node (ref "U$2") (pin "DL1") (pinfunction "1_DL1") (pintype "bidirectional"))
    )
    (net (code "53") (name "MD10") (class "Default")
      (node (ref "E46") (pin "4") (pinfunction "I0_4") (pintype "input"))
      (node (ref "U$2") (pin "DM1") (pinfunction "1_DM1") (pintype "bidirectional"))
    )
    (net (code "54") (name "MD11") (class "Default")
      (node (ref "E46") (pin "9") (pinfunction "I0_9") (pintype "input"))
      (node (ref "U$2") (pin "DP1") (pinfunction "1_DP1") (pintype "bidirectional"))
    )
    (net (code "55") (name "Net-(C58-Pad2)") (class "Default")
      (node (ref "C58") (pin "2") (pinfunction "2_2") (pintype "passive"))
      (node (ref "C67") (pin "1") (pinfunction "1_1") (pintype "passive"))
      (node (ref "Y1") (pin "1") (pinfunction "1_1") (pintype "passive"))
    )
    (net (code "56") (name "Net-(C61-Pad2)") (class "Default")
      (node (ref "C61") (pin "2") (pinfunction "2_2") (pintype "passive"))
      (node (ref "R4") (pin "2") (pinfunction "2_2") (pintype "passive"))
      (node (ref "T1") (pin "1") (pinfunction "1_1") (pintype "passive"))
      (node (ref "T1") (pin "5") (pinfunction "5_5") (pintype "passive"))
    )
    (net (code "57") (name "Net-(C66-Pad+)") (class "Default")
      (node (ref "C66") (pin "+") (pinfunction "+_+") (pintype "passive"))
      (node (ref "D7") (pin "A") (pinfunction "A_A") (pintype "passive"))
      (node (ref "D8") (pin "C") (pinfunction "C_C") (pintype "passive"))
      (node (ref "R18") (pin "1") (pinfunction "1_1") (pintype "passive"))
      (node (ref "R22") (pin "2") (pinfunction "2_2") (pintype "passive"))
    )
    (net (code "58") (name "Net-(D1-PadA)") (class "Default")
      (node (ref "D1") (pin "A") (pinfunction "A_A") (pintype "passive"))
      (node (ref "R5") (pin "1") (pinfunction "1_1") (pintype "passive"))
      (node (ref "R7") (pin "1") (pinfunction "1_1") (pintype "passive"))
      (node (ref "T1") (pin "9") (pinfunction "9_9") (pintype "passive"))
    )
    (net (code "59") (name "Net-(D2-PadA)") (class "Default")
      (node (ref "D2") (pin "A") (pinfunction "A_A") (pintype "passive"))
      (node (ref "D3") (pin "C") (pinfunction "C_C") (pintype "passive"))
    )
    (net (code "60") (name "Net-(D3-PadA)") (class "Default")
      (node (ref "D3") (pin "A") (pinfunction "A_A") (pintype "passive"))
      (node (ref "D4") (pin "C") (pinfunction "C_C") (pintype "passive"))
    )
    (net (code "61") (name "Net-(D10-PadC)") (class "Default")
      (node (ref "D10") (pin "C") (pinfunction "C_C") (pintype "passive"))
      (node (ref "D11") (pin "A") (pinfunction "A_A") (pintype "passive"))
    )
    (net (code "62") (name "Net-(D11-PadC)") (class "Default")
      (node (ref "D11") (pin "C") (pinfunction "C_C") (pintype "passive"))
      (node (ref "D12") (pin "A") (pinfunction "A_A") (pintype "passive"))
    )
    (net (code "63") (name "Net-(D13-PadA)") (class "Default")
      (node (ref "D13") (pin "A") (pinfunction "A_A") (pintype "passive"))
      (node (ref "D14") (pin "C") (pinfunction "C_C") (pintype "passive"))
    )
    (net (code "64") (name "Net-(D14-PadA)") (class "Default")
      (node (ref "D14") (pin "A") (pinfunction "A_A") (pintype "passive"))
      (node (ref "D15") (pin "C") (pinfunction "C_C") (pintype "passive"))
    )
    (net (code "65") (name "Net-(E1A-O)") (class "Default")
      (node (ref "C") (pin "1") (pinfunction "1_1") (pintype "passive"))
      (node (ref "E1") (pin "3") (pinfunction "O_3") (pintype "output"))
      (node (ref "JC13") (pin "2") (pinfunction "2_2") (pintype "passive"))
    )
    (net (code "66") (name "Net-(E1B-O)") (class "Default")
      (node (ref "A") (pin "1") (pinfunction "1_1") (pintype "passive"))
      (node (ref "E1") (pin "2") (pinfunction "O_2") (pintype "output"))
      (node (ref "JA12") (pin "1") (pinfunction "1_1") (pintype "passive"))
      (node (ref "JA13") (pin "2") (pinfunction "2_2") (pintype "passive"))
    )
    (net (code "67") (name "Net-(E1C-O)") (class "Default")
      (node (ref "B") (pin "1") (pinfunction "1_1") (pintype "passive"))
      (node (ref "E1") (pin "14") (pinfunction "O_14") (pintype "output"))
      (node (ref "JB12") (pin "1") (pinfunction "1_1") (pintype "passive"))
      (node (ref "JB13") (pin "2") (pinfunction "2_2") (pintype "passive"))
    )
    (net (code "68") (name "Net-(E1D-O)") (class "Default")
      (node (ref "E1") (pin "13") (pinfunction "O_13") (pintype "output"))
      (node (ref "E48") (pin "11") (pinfunction "CLK_11") (pintype "input"))
    )
    (net (code "69") (name "Net-(E2B-I1)") (class "Default")
      (node (ref "E2") (pin "6") (pinfunction "I1_6") (pintype "input"))
      (node (ref "E6") (pin "9") (pinfunction "Q2_9") (pintype "output"))
    )
    (net (code "70") (name "Net-(E2C-I0)") (class "Default")
      (node (ref "E2") (pin "8") (pinfunction "I0_8") (pintype "input"))
      (node (ref "E6") (pin "7") (pinfunction "Q1_7") (pintype "output"))
    )
    (net (code "71") (name "Net-(E5A-CKB)") (class "Default")
      (node (ref "E5") (pin "1") (pinfunction "CKB_1") (pintype "input"))
      (node (ref "E5") (pin "12") (pinfunction "QA_12") (pintype "output"))
    )
    (net (code "72") (name "Net-(E8B-D)") (class "Default")
      (node (ref "E8") (pin "12") (pinfunction "D_12") (pintype "input"))
      (node (ref "E8") (pin "8") (pinfunction "~{Q}_8") (pintype "output"))
    )
    (net (code "73") (name "Net-(E9A-I0)") (class "Default")
      (node (ref "E9") (pin "4") (pinfunction "I0_4") (pintype "input"))
      (node (ref "F") (pin "1") (pinfunction "1_1") (pintype "passive"))
      (node (ref "JF12") (pin "2") (pinfunction "2_2") (pintype "passive"))
    )
    (net (code "74") (name "Net-(E9A-I2)") (class "Default")
      (node (ref "E") (pin "4") (pinfunction "4_4") (pintype "passive"))
      (node (ref "E9") (pin "6") (pinfunction "I2_6") (pintype "input"))
      (node (ref "JE24") (pin "1") (pinfunction "1_1") (pintype "passive"))
    )
    (net (code "75") (name "Net-(E9A-I3)") (class "Default")
      (node (ref "A") (pin "3") (pinfunction "3_3") (pintype "passive"))
      (node (ref "E9") (pin "9") (pinfunction "I3_9") (pintype "input"))
      (node (ref "JA13") (pin "1") (pinfunction "1_1") (pintype "passive"))
    )
    (net (code "76") (name "Net-(E9A-I4)") (class "Default")
      (node (ref "C") (pin "2") (pinfunction "2_2") (pintype "passive"))
      (node (ref "E9") (pin "10") (pinfunction "I4_10") (pintype "input"))
      (node (ref "JC24") (pin "2") (pinfunction "2_2") (pintype "passive"))
    )
    (net (code "77") (name "Net-(E9A-I5)") (class "Default")
      (node (ref "B") (pin "2") (pinfunction "2_2") (pintype "passive"))
      (node (ref "E9") (pin "11") (pinfunction "I5_11") (pintype "input"))
      (node (ref "JB12") (pin "2") (pinfunction "2_2") (pintype "passive"))
    )
    (net (code "78") (name "Net-(E9A-I6)") (class "Default")
      (node (ref "D") (pin "2") (pinfunction "2_2") (pintype "passive"))
      (node (ref "E9") (pin "12") (pinfunction "I6_12") (pintype "input"))
      (node (ref "JD24") (pin "2") (pinfunction "2_2") (pintype "passive"))
    )
    (net (code "79") (name "Net-(E10A-C)") (class "Default")
      (node (ref "E10") (pin "6") (pinfunction "C_6") (pintype "input"))
      (node (ref "E11") (pin "4") (pinfunction "O_4") (pintype "output"))
      (node (ref "E6") (pin "6") (pinfunction "C_6") (pintype "input"))
    )
    (net (code "80") (name "Net-(E10A-D)") (class "Default")
      (node (ref "E10") (pin "4") (pinfunction "D_4") (pintype "input"))
      (node (ref "E2") (pin "2") (pinfunction "I0_2") (pintype "input"))
      (node (ref "E6") (pin "11") (pinfunction "Q3_11") (pintype "output"))
    )
    (net (code "81") (name "Net-(E10A-Q0)") (class "Default")
      (node (ref "E10") (pin "5") (pinfunction "Q0_5") (pintype "output"))
      (node (ref "E15") (pin "12") (pinfunction "I1_12") (pintype "input"))
    )
    (net (code "82") (name "Net-(E10A-Q1)") (class "Default")
      (node (ref "E10") (pin "7") (pinfunction "Q1_7") (pintype "output"))
      (node (ref "E15") (pin "8") (pinfunction "I0_8") (pintype "input"))
    )
    (net (code "83") (name "Net-(E10A-Q2)") (class "Default")
      (node (ref "E10") (pin "9") (pinfunction "Q2_9") (pintype "output"))
      (node (ref "E15") (pin "6") (pinfunction "I1_6") (pintype "input"))
    )
    (net (code "84") (name "Net-(E10A-Q3)") (class "Default")
      (node (ref "E10") (pin "11") (pinfunction "Q3_11") (pintype "output"))
      (node (ref "E15") (pin "2") (pinfunction "I0_2") (pintype "input"))
    )
    (net (code "85") (name "Net-(E11A-O)") (class "Default")
      (node (ref "E11") (pin "1") (pinfunction "O_1") (pintype "output"))
      (node (ref "E39") (pin "9") (pinfunction "I2_9") (pintype "input"))
    )
    (net (code "86") (name "Net-(E11B-I1)") (class "Default")
      (node (ref "E11") (pin "10") (pinfunction "O_10") (pintype "output"))
      (node (ref "E11") (pin "6") (pinfunction "I1_6") (pintype "input"))
    )
    (net (code "87") (name "Net-(E11D-O)") (class "Default")
      (node (ref "E11") (pin "13") (pinfunction "O_13") (pintype "output"))
      (node (ref "E3") (pin "11") (pinfunction "CLK_11") (pintype "input"))
    )
    (net (code "88") (name "Net-(E12B-O)") (class "Default")
      (node (ref "E12") (pin "6") (pinfunction "O_6") (pintype "output"))
      (node (ref "E8") (pin "1") (pinfunction "CLR_1") (pintype "input"))
    )
    (net (code "89") (name "Net-(E12C-O)") (class "Default")
      (node (ref "E12") (pin "8") (pinfunction "O_8") (pintype "output"))
      (node (ref "E3") (pin "2") (pinfunction "D_2") (pintype "input"))
    )
    (net (code "90") (name "Net-(E14A-I0)") (class "Default")
      (node (ref "E") (pin "1") (pinfunction "1_1") (pintype "passive"))
      (node (ref "E14") (pin "4") (pinfunction "I0_4") (pintype "input"))
      (node (ref "JE13") (pin "2") (pinfunction "2_2") (pintype "passive"))
    )
    (net (code "91") (name "Net-(E14A-I1)") (class "Default")
      (node (ref "E14") (pin "5") (pinfunction "I1_5") (pintype "input"))
      (node (ref "F") (pin "4") (pinfunction "4_4") (pintype "passive"))
      (node (ref "JF24") (pin "1") (pinfunction "1_1") (pintype "passive"))
    )
    (net (code "92") (name "Net-(E14A-I2)") (class "Default")
      (node (ref "D") (pin "3") (pinfunction "3_3") (pintype "passive"))
      (node (ref "E14") (pin "6") (pinfunction "I2_6") (pintype "input"))
      (node (ref "JD13") (pin "1") (pinfunction "1_1") (pintype "passive"))
    )
    (net (code "93") (name "Net-(E14A-I3)") (class "Default")
      (node (ref "B") (pin "3") (pinfunction "3_3") (pintype "passive"))
      (node (ref "E14") (pin "9") (pinfunction "I3_9") (pintype "input"))
      (node (ref "JB13") (pin "1") (pinfunction "1_1") (pintype "passive"))
    )
    (net (code "94") (name "Net-(E14A-I4)") (class "Default")
      (node (ref "C") (pin "3") (pinfunction "3_3") (pintype "passive"))
      (node (ref "E14") (pin "10") (pinfunction "I4_10") (pintype "input"))
      (node (ref "JC13") (pin "1") (pinfunction "1_1") (pintype "passive"))
    )
    (net (code "95") (name "Net-(E14A-I5)") (class "Default")
      (node (ref "E14") (pin "11") (pinfunction "I5_11") (pintype "input"))
      (node (ref "E34") (pin "3") (pinfunction "O_3") (pintype "output"))
      (node (ref "E34") (pin "6") (pinfunction "I0_6") (pintype "input"))
      (node (ref "E9") (pin "5") (pinfunction "I1_5") (pintype "input"))
    )
    (net (code "96") (name "Net-(E14A-I6)") (class "Default")
      (node (ref "A") (pin "2") (pinfunction "2_2") (pintype "passive"))
      (node (ref "E14") (pin "12") (pinfunction "I6_12") (pintype "input"))
      (node (ref "JA12") (pin "2") (pinfunction "2_2") (pintype "passive"))
    )
    (net (code "97") (name "Net-(E14A-O)") (class "Default")
      (node (ref "E14") (pin "3") (pinfunction "O_3") (pintype "output"))
      (node (ref "E23") (pin "5") (pinfunction "I1_5") (pintype "input"))
      (node (ref "E33") (pin "8") (pinfunction "I0_8") (pintype "input"))
      (node (ref "E33") (pin "9") (pinfunction "I1_9") (pintype "input"))
      (node (ref "E37") (pin "2") (pinfunction "I0_2") (pintype "input"))
      (node (ref "E37") (pin "3") (pinfunction "I1_3") (pintype "input"))
    )
    (net (code "98") (name "Net-(E16A-D)") (class "Default")
      (node (ref "E16") (pin "2") (pinfunction "D_2") (pintype "input"))
      (node (ref "E35") (pin "8") (pinfunction "O_8") (pintype "output"))
    )
    (net (code "99") (name "Net-(E17A-O)") (class "Default")
      (node (ref "E17") (pin "3") (pinfunction "O_3") (pintype "output"))
      (node (ref "E21") (pin "13") (pinfunction "I_13") (pintype "input"))
    )
    (net (code "100") (name "Net-(E17A-RC)") (class "Default")
      (node (ref "E17") (pin "2") (pinfunction "RC_2") (pintype "input"))
      (node (ref "R23") (pin "1") (pinfunction "1_1") (pintype "passive"))
    )
    (net (code "101") (name "Net-(E18A-CKA)") (class "Default")
      (node (ref "E18") (pin "14") (pinfunction "CKA_14") (pintype "input"))
      (node (ref "G12") (pin "2") (pinfunction "2_2") (pintype "passive"))
      (node (ref "G34") (pin "2") (pinfunction "2_2") (pintype "passive"))
      (node (ref "G56") (pin "2") (pinfunction "2_2") (pintype "passive"))
      (node (ref "G78") (pin "2") (pinfunction "2_2") (pintype "passive"))
      (node (ref "G910") (pin "2") (pinfunction "2_2") (pintype "passive"))
      (node (ref "U$2") (pin "AA1") (pinfunction "1_AA1") (pintype "bidirectional"))
    )
    (net (code "102") (name "Net-(E18A-QD)") (class "Default")
      (node (ref "E18") (pin "11") (pinfunction "QD_11") (pintype "output"))
      (node (ref "H12") (pin "1") (pinfunction "1_1") (pintype "passive"))
      (node (ref "H123") (pin "1") (pinfunction "1_1") (pintype "passive"))
    )
    (net (code "103") (name "Net-(E19A-I1)") (class "Default")
      (node (ref "E19") (pin "2") (pinfunction "I1_2") (pintype "input"))
      (node (ref "E21") (pin "10") (pinfunction "O_10") (pintype "output"))
    )
    (net (code "104") (name "Net-(E19B-I0)") (class "Default")
      (node (ref "E19") (pin "11") (pinfunction "I2_11") (pintype "input"))
      (node (ref "E19") (pin "3") (pinfunction "I0_3") (pintype "input"))
      (node (ref "E24") (pin "8") (pinfunction "O_8") (pintype "output"))
    )
    (net (code "105") (name "Net-(E19B-I2)") (class "Default")
      (node (ref "E19") (pin "10") (pinfunction "I1_10") (pintype "input"))
      (node (ref "E19") (pin "5") (pinfunction "I2_5") (pintype "input"))
      (node (ref "E19") (pin "9") (pinfunction "I0_9") (pintype "input"))
      (node (ref "E24") (pin "6") (pinfunction "O_6") (pintype "output"))
    )
    (net (code "106") (name "Net-(E20A-D)") (class "Default")
      (node (ref "E20") (pin "2") (pinfunction "D_2") (pintype "input"))
      (node (ref "E25") (pin "8") (pinfunction "O_8") (pintype "output"))
    )
    (net (code "107") (name "Net-(E21A-I)") (class "Default")
      (node (ref "E21") (pin "1") (pinfunction "I_1") (pintype "input"))
      (node (ref "E39") (pin "8") (pinfunction "O_8") (pintype "output"))
    )
    (net (code "108") (name "Net-(E21A-O)") (class "Default")
      (node (ref "E21") (pin "2") (pinfunction "O_2") (pintype "output"))
      (node (ref "E7") (pin "3") (pinfunction "CLK_3") (pintype "input"))
    )
    (net (code "109") (name "Net-(E21B-O)") (class "Default")
      (node (ref "E21") (pin "4") (pinfunction "O_4") (pintype "output"))
      (node (ref "E29") (pin "11") (pinfunction "CLK_11") (pintype "input"))
    )
    (net (code "110") (name "Net-(E21C-O)") (class "Default")
      (node (ref "E21") (pin "6") (pinfunction "O_6") (pintype "output"))
      (node (ref "E26") (pin "6") (pinfunction "C_6") (pintype "input"))
    )
    (net (code "111") (name "Net-(E21D-O)") (class "Default")
      (node (ref "E21") (pin "8") (pinfunction "O_8") (pintype "output"))
      (node (ref "E6") (pin "4") (pinfunction "D_4") (pintype "input"))
    )
    (net (code "112") (name "Net-(E22A-QD)") (class "Default")
      (node (ref "E22") (pin "7") (pinfunction "QD_7") (pintype "output"))
      (node (ref "E5") (pin "14") (pinfunction "CKA_14") (pintype "input"))
    )
    (net (code "113") (name "Net-(E22A-UP)") (class "Default")
      (node (ref "E22") (pin "5") (pinfunction "UP_5") (pintype "input"))
      (node (ref "R6") (pin "2") (pinfunction "2_2") (pintype "passive"))
    )
    (net (code "114") (name "Net-(E23A-I0)") (class "Default")
      (node (ref "E23") (pin "4") (pinfunction "I0_4") (pintype "input"))
      (node (ref "E37") (pin "5") (pinfunction "I0_5") (pintype "input"))
      (node (ref "E37") (pin "6") (pinfunction "I1_6") (pintype "input"))
      (node (ref "E42") (pin "13") (pinfunction "I_13") (pintype "input"))
      (node (ref "E9") (pin "3") (pinfunction "O_3") (pintype "output"))
    )
    (net (code "115") (name "Net-(E23B-O)") (class "Default")
      (node (ref "D") (pin "1") (pinfunction "1_1") (pintype "passive"))
      (node (ref "E23") (pin "2") (pinfunction "O_2") (pintype "output"))
      (node (ref "JD13") (pin "2") (pinfunction "2_2") (pintype "passive"))
    )
    (net (code "116") (name "Net-(E23C-O)") (class "Default")
      (node (ref "E23") (pin "14") (pinfunction "O_14") (pintype "output"))
      (node (ref "F") (pin "2") (pinfunction "2_2") (pintype "passive"))
      (node (ref "JF12") (pin "1") (pinfunction "1_1") (pintype "passive"))
      (node (ref "JF24") (pin "2") (pinfunction "2_2") (pintype "passive"))
    )
    (net (code "117") (name "Net-(E23D-O)") (class "Default")
      (node (ref "E") (pin "2") (pinfunction "2_2") (pintype "passive"))
      (node (ref "E23") (pin "13") (pinfunction "O_13") (pintype "output"))
      (node (ref "JE24") (pin "2") (pinfunction "2_2") (pintype "passive"))
    )
    (net (code "118") (name "Net-(E24A-I0)") (class "Default")
      (node (ref "E24") (pin "1") (pinfunction "I0_1") (pintype "input"))
      (node (ref "E28") (pin "9") (pinfunction "Q2_9") (pintype "output"))
    )
    (net (code "119") (name "Net-(E24A-I2)") (class "Default")
      (node (ref "E24") (pin "4") (pinfunction "I2_4") (pintype "input"))
      (node (ref "E28") (pin "5") (pinfunction "Q0_5") (pintype "output"))
    )
    (net (code "120") (name "Net-(E24A-I3)") (class "Default")
      (node (ref "E24") (pin "5") (pinfunction "I3_5") (pintype "input"))
      (node (ref "E28") (pin "7") (pinfunction "Q1_7") (pintype "output"))
    )
    (net (code "121") (name "Net-(E24B-I0)") (class "Default")
      (node (ref "E24") (pin "9") (pinfunction "I0_9") (pintype "input"))
      (node (ref "E31") (pin "5") (pinfunction "Q0_5") (pintype "output"))
    )
    (net (code "122") (name "Net-(E24B-I1)") (class "Default")
      (node (ref "E24") (pin "10") (pinfunction "I1_10") (pintype "input"))
      (node (ref "E31") (pin "7") (pinfunction "Q1_7") (pintype "output"))
    )
    (net (code "123") (name "Net-(E24B-I2)") (class "Default")
      (node (ref "E24") (pin "12") (pinfunction "I2_12") (pintype "input"))
      (node (ref "E31") (pin "9") (pinfunction "Q2_9") (pintype "output"))
    )
    (net (code "124") (name "Net-(E24B-I3)") (class "Default")
      (node (ref "E24") (pin "13") (pinfunction "I3_13") (pintype "input"))
      (node (ref "E28") (pin "11") (pinfunction "Q3_11") (pintype "output"))
      (node (ref "E31") (pin "4") (pinfunction "D_4") (pintype "input"))
    )
    (net (code "125") (name "Net-(E25B-I4)") (class "Default")
      (node (ref "DL1") (pin "3") (pinfunction "3_3") (pintype "passive"))
      (node (ref "E25") (pin "5") (pinfunction "I4_5") (pintype "input"))
      (node (ref "R20") (pin "1") (pinfunction "1_1") (pintype "passive"))
    )
    (net (code "126") (name "Net-(E26A-Q0)") (class "Default")
      (node (ref "E26") (pin "5") (pinfunction "Q0_5") (pintype "output"))
      (node (ref "J23") (pin "3") (pinfunction "3_3") (pintype "passive"))
    )
    (net (code "127") (name "Net-(E26A-Q2)") (class "Default")
      (node (ref "E26") (pin "9") (pinfunction "Q2_9") (pintype "output"))
      (node (ref "J23") (pin "1") (pinfunction "1_1") (pintype "passive"))
      (node (ref "JJ23") (pin "1") (pinfunction "1_1") (pintype "passive"))
    )
    (net (code "128") (name "Net-(E27A-O)") (class "Default")
      (node (ref "E27") (pin "3") (pinfunction "O_3") (pintype "output"))
      (node (ref "E28") (pin "2") (pinfunction "I1_2") (pintype "input"))
    )
    (net (code "129") (name "Net-(E27B-O)") (class "Default")
      (node (ref "E27") (pin "2") (pinfunction "O_2") (pintype "output"))
      (node (ref "E28") (pin "3") (pinfunction "I0_3") (pintype "input"))
    )
    (net (code "130") (name "Net-(E27C-O)") (class "Default")
      (node (ref "E27") (pin "14") (pinfunction "O_14") (pintype "output"))
      (node (ref "E28") (pin "14") (pinfunction "I3_14") (pintype "input"))
    )
    (net (code "131") (name "Net-(E27D-O)") (class "Default")
      (node (ref "E27") (pin "13") (pinfunction "O_13") (pintype "output"))
      (node (ref "E28") (pin "15") (pinfunction "I2_15") (pintype "input"))
    )
    (net (code "132") (name "Net-(E30A-O)") (class "Default")
      (node (ref "E30") (pin "3") (pinfunction "O_3") (pintype "output"))
      (node (ref "E31") (pin "2") (pinfunction "I1_2") (pintype "input"))
    )
    (net (code "133") (name "Net-(E30B-O)") (class "Default")
      (node (ref "E30") (pin "2") (pinfunction "O_2") (pintype "output"))
      (node (ref "E31") (pin "3") (pinfunction "I0_3") (pintype "input"))
    )
    (net (code "134") (name "Net-(E30C-O)") (class "Default")
      (node (ref "E30") (pin "14") (pinfunction "O_14") (pintype "output"))
      (node (ref "E31") (pin "14") (pinfunction "I3_14") (pintype "input"))
    )
    (net (code "135") (name "Net-(E30D-O)") (class "Default")
      (node (ref "E30") (pin "13") (pinfunction "O_13") (pintype "output"))
      (node (ref "E31") (pin "15") (pinfunction "I2_15") (pintype "input"))
    )
    (net (code "136") (name "Net-(E34B-O)") (class "Default")
      (node (ref "E34") (pin "2") (pinfunction "O_2") (pintype "output"))
      (node (ref "E38") (pin "12") (pinfunction "D_12") (pintype "input"))
    )
    (net (code "137") (name "Net-(E35B-O)") (class "Default")
      (node (ref "E35") (pin "6") (pinfunction "O_6") (pintype "output"))
      (node (ref "E47") (pin "2") (pinfunction "I0_2") (pintype "input"))
    )
    (net (code "138") (name "Net-(E35D-I0)") (class "Default")
      (node (ref "E35") (pin "12") (pinfunction "I0_12") (pintype "input"))
      (node (ref "E35") (pin "13") (pinfunction "I1_13") (pintype "input"))
      (node (ref "E36") (pin "14") (pinfunction "O_14") (pintype "output"))
      (node (ref "E46") (pin "11") (pinfunction "I0_11") (pintype "input"))
      (node (ref "E46") (pin "12") (pinfunction "I1_12") (pintype "input"))
    )
    (net (code "139") (name "Net-(E36B-I0)") (class "Default")
      (node (ref "C65") (pin "1") (pinfunction "1_1") (pintype "passive"))
      (node (ref "E36") (pin "6") (pinfunction "I0_6") (pintype "input"))
      (node (ref "E36") (pin "7") (pinfunction "I1_7") (pintype "input"))
      (node (ref "R18") (pin "2") (pinfunction "2_2") (pintype "passive"))
      (node (ref "R19") (pin "1") (pinfunction "1_1") (pintype "passive"))
    )
    (net (code "140") (name "Net-(E36D-O)") (class "Default")
      (node (ref "E36") (pin "13") (pinfunction "O_13") (pintype "output"))
      (node (ref "E7") (pin "1") (pinfunction "CLR_1") (pintype "input"))
    )
    (net (code "141") (name "Net-(E37C-I0)") (class "Default")
      (node (ref "E37") (pin "8") (pinfunction "I0_8") (pintype "input"))
      (node (ref "E37") (pin "9") (pinfunction "I1_9") (pintype "input"))
      (node (ref "E42") (pin "8") (pinfunction "O_8") (pintype "output"))
    )
    (net (code "142") (name "Net-(E38A-PRE)") (class "Default")
      (node (ref "E38") (pin "4") (pinfunction "PRE_4") (pintype "input"))
      (node (ref "E42") (pin "6") (pinfunction "O_6") (pintype "output"))
    )
    (net (code "143") (name "Net-(E39B-I1)") (class "Default")
      (node (ref "E39") (pin "2") (pinfunction "I1_2") (pintype "input"))
      (node (ref "E45") (pin "10") (pinfunction "O_10") (pintype "output"))
    )
    (net (code "144") (name "Net-(E39B-O)") (class "Default")
      (node (ref "E39") (pin "6") (pinfunction "O_6") (pintype "output"))
      (node (ref "E42") (pin "9") (pinfunction "I_9") (pintype "input"))
    )
    (net (code "145") (name "Net-(E40A-A)") (class "Default")
      (node (ref "E40") (pin "15") (pinfunction "A_15") (pintype "input"))
      (node (ref "E43") (pin "15") (pinfunction "A_15") (pintype "input"))
      (node (ref "E46") (pin "14") (pinfunction "O_14") (pintype "output"))
    )
    (net (code "146") (name "Net-(E40A-B)") (class "Default")
      (node (ref "E40") (pin "14") (pinfunction "B_14") (pintype "input"))
      (node (ref "E43") (pin "14") (pinfunction "B_14") (pintype "input"))
      (node (ref "E46") (pin "3") (pinfunction "O_3") (pintype "output"))
    )
    (net (code "147") (name "Net-(E40A-C)") (class "Default")
      (node (ref "E40") (pin "1") (pinfunction "C_1") (pintype "input"))
      (node (ref "E43") (pin "1") (pinfunction "C_1") (pintype "input"))
      (node (ref "E46") (pin "2") (pinfunction "O_2") (pintype "output"))
    )
    (net (code "148") (name "Net-(E41A-O)") (class "Default")
      (node (ref "E41") (pin "3") (pinfunction "O_3") (pintype "output"))
      (node (ref "E42") (pin "5") (pinfunction "I_5") (pintype "input"))
    )
    (net (code "149") (name "Net-(E42E-I)") (class "Default")
      (node (ref "E42") (pin "11") (pinfunction "I_11") (pintype "input"))
      (node (ref "E45") (pin "4") (pinfunction "O_4") (pintype "output"))
    )
    (net (code "150") (name "Net-(E47A-O)") (class "Default")
      (node (ref "E47") (pin "1") (pinfunction "O_1") (pintype "output"))
      (node (ref "E48") (pin "1") (pinfunction "CLR_1") (pintype "input"))
    )
    (net (code "151") (name "Net-(Q1-B)") (class "Default")
      (node (ref "C58") (pin "1") (pinfunction "1_1") (pintype "passive"))
      (node (ref "C59") (pin "1") (pinfunction "1_1") (pintype "passive"))
      (node (ref "Q1") (pin "2") (pinfunction "B_2") (pintype "passive"))
      (node (ref "R3") (pin "1") (pinfunction "1_1") (pintype "passive"))
    )
    (net (code "152") (name "Net-(Q1-E)") (class "Default")
      (node (ref "C59") (pin "2") (pinfunction "2_2") (pintype "passive"))
      (node (ref "C60") (pin "1") (pinfunction "1_1") (pintype "passive"))
      (node (ref "C61") (pin "1") (pinfunction "1_1") (pintype "passive"))
      (node (ref "Q1") (pin "1") (pinfunction "E_1") (pintype "passive"))
      (node (ref "R4") (pin "1") (pinfunction "1_1") (pintype "passive"))
    )
    (net (code "153") (name "Net-(Q2-E)") (class "Default")
      (node (ref "D4") (pin "A") (pinfunction "A_A") (pintype "passive"))
      (node (ref "Q2") (pin "1") (pinfunction "E_1") (pintype "passive"))
      (node (ref "R8") (pin "1") (pinfunction "1_1") (pintype "passive"))
    )
    (net (code "154") (name "Net-(Q3-B)") (class "Default")
      (node (ref "C63") (pin "1") (pinfunction "1_1") (pintype "passive"))
      (node (ref "Q3") (pin "2") (pinfunction "B_2") (pintype "passive"))
      (node (ref "R13") (pin "2") (pinfunction "2_2") (pintype "passive"))
    )
    (net (code "155") (name "Net-(Q3-C)") (class "Default")
      (node (ref "C63") (pin "2") (pinfunction "2_2") (pintype "passive"))
      (node (ref "D9") (pin "A") (pinfunction "A_A") (pintype "passive"))
      (node (ref "Q3") (pin "3") (pinfunction "C_3") (pintype "passive"))
      (node (ref "R12") (pin "2") (pinfunction "2_2") (pintype "passive"))
    )
    (net (code "156") (name "Net-(R5-Pad2)") (class "Default")
      (node (ref "R5") (pin "2") (pinfunction "2_2") (pintype "passive"))
      (node (ref "R6") (pin "1") (pinfunction "1_1") (pintype "passive"))
      (node (ref "T1") (pin "16") (pinfunction "16_16") (pintype "passive"))
    )
    (net (code "157") (name "Net-(T1-Pad2)") (class "Default")
      (node (ref "T1") (pin "2") (pinfunction "2_2") (pintype "passive"))
      (node (ref "T1") (pin "3") (pinfunction "3_3") (pintype "passive"))
    )
    (net (code "158") (name "Net-(T1-Pad6)") (class "Default")
      (node (ref "T1") (pin "6") (pinfunction "6_6") (pintype "passive"))
      (node (ref "T1") (pin "7") (pinfunction "7_7") (pintype "passive"))
    )
    (net (code "159") (name "Net-(T1-Pad10)") (class "Default")
      (node (ref "T1") (pin "10") (pinfunction "10_10") (pintype "passive"))
      (node (ref "T1") (pin "11") (pinfunction "11_11") (pintype "passive"))
    )
    (net (code "160") (name "Net-(T1-Pad12)") (class "Default")
      (node (ref "T1") (pin "12") (pinfunction "12_12") (pintype "passive"))
      (node (ref "T1") (pin "13") (pinfunction "13_13") (pintype "passive"))
    )
    (net (code "161") (name "Net-(T1-Pad14)") (class "Default")
      (node (ref "T1") (pin "14") (pinfunction "14_14") (pintype "passive"))
      (node (ref "T1") (pin "15") (pinfunction "15_15") (pintype "passive"))
    )
    (net (code "162") (name "POWER_OK") (class "Default")
      (node (ref "E36") (pin "12") (pinfunction "I1_12") (pintype "input"))
      (node (ref "U$2") (pin "BV2") (pinfunction "1_BV2") (pintype "bidirectional"))
    )
    (net (code "163") (name "READER_RUN+") (class "Default")
      (node (ref "C62") (pin "1") (pinfunction "1_1") (pintype "passive"))
      (node (ref "D5") (pin "A") (pinfunction "A_A") (pintype "passive"))
      (node (ref "J1") (pin "PP") (pinfunction "35_PP") (pintype "bidirectional"))
      (node (ref "Q2") (pin "3") (pinfunction "C_3") (pintype "passive"))
    )
    (net (code "164") (name "READER_RUN-") (class "Default")
      (node (ref "J1") (pin "EE") (pinfunction "27_EE") (pintype "bidirectional"))
      (node (ref "R9") (pin "2") (pinfunction "2_2") (pintype "passive"))
    )
    (net (code "165") (name "RTSDTR") (class "Default")
      (node (ref "E32") (pin "6") (pinfunction "O_6") (pintype "output"))
      (node (ref "J1") (pin "DD") (pinfunction "26_DD") (pintype "bidirectional"))
      (node (ref "J1") (pin "V") (pinfunction "18_V") (pintype "bidirectional"))
    )
    (net (code "166") (name "RX7") (class "Default")
      (node (ref "E1") (pin "11") (pinfunction "I0_11") (pintype "input"))
      (node (ref "E1") (pin "12") (pinfunction "I1_12") (pintype "input"))
      (node (ref "E2") (pin "12") (pinfunction "I1_12") (pintype "input"))
      (node (ref "E6") (pin "5") (pinfunction "Q0_5") (pintype "output"))
      (node (ref "R24") (pin "1") (pinfunction "1_1") (pintype "passive"))
    )
    (net (code "167") (name "RX20MA_DATA") (class "Default")
      (node (ref "C65") (pin "2") (pinfunction "2_2") (pintype "passive"))
      (node (ref "E36") (pin "2") (pinfunction "O_2") (pintype "output"))
      (node (ref "J1") (pin "H") (pinfunction "7_H") (pintype "bidirectional"))
      (node (ref "R19") (pin "2") (pinfunction "2_2") (pintype "passive"))
    )
    (net (code "168") (name "RX_20MA+") (class "Default")
      (node (ref "C64") (pin "1") (pinfunction "1_1") (pintype "passive"))
      (node (ref "J1") (pin "K") (pinfunction "9_K") (pintype "bidirectional"))
      (node (ref "R16") (pin "1") (pinfunction "1_1") (pintype "passive"))
      (node (ref "R22") (pin "1") (pinfunction "1_1") (pintype "passive"))
      (node (ref "U$2") (pin "BB1") (pinfunction "1_BB1") (pintype "bidirectional"))
    )
    (net (code "169") (name "RX_20MA-") (class "Default")
      (node (ref "C64") (pin "2") (pinfunction "2_2") (pintype "passive"))
      (node (ref "J1") (pin "S") (pinfunction "15_S") (pintype "bidirectional"))
      (node (ref "R17") (pin "2") (pinfunction "2_2") (pintype "passive"))
    )
    (net (code "170") (name "RX_ACTIVE") (class "Default")
      (node (ref "E12") (pin "1") (pinfunction "I0_1") (pintype "input"))
      (node (ref "E7") (pin "11") (pinfunction "CLK_11") (pintype "input"))
      (node (ref "E7") (pin "5") (pinfunction "Q_5") (pintype "output"))
      (node (ref "U$2") (pin "AB1") (pinfunction "1_AB1") (pintype "bidirectional"))
    )
    (net (code "171") (name "RX_BOT") (class "Default")
      (node (ref "E10") (pin "12") (pinfunction "Q4_12") (pintype "output"))
      (node (ref "E48") (pin "2") (pinfunction "D_2") (pintype "input"))
      (node (ref "E8") (pin "2") (pinfunction "D_2") (pintype "input"))
    )
    (net (code "172") (name "RX_DATA") (class "Default")
      (node (ref "E21") (pin "12") (pinfunction "O_12") (pintype "output"))
      (node (ref "J1") (pin "M") (pinfunction "11_M") (pintype "bidirectional"))
    )
    (net (code "173") (name "RX_DIV") (class "Default")
      (node (ref "E12") (pin "9") (pinfunction "I0_9") (pintype "input"))
      (node (ref "E3") (pin "5") (pinfunction "Q_5") (pintype "output"))
    )
    (net (code "174") (name "RX_DIV8") (class "Default")
      (node (ref "E12") (pin "2") (pinfunction "I1_2") (pintype "input"))
      (node (ref "E12") (pin "5") (pinfunction "I1_5") (pintype "input"))
      (node (ref "E8") (pin "9") (pinfunction "Q_9") (pintype "output"))
    )
    (net (code "175") (name "RX_LAST") (class "Default")
      (node (ref "E36") (pin "3") (pinfunction "O_3") (pintype "output"))
      (node (ref "E4") (pin "1") (pinfunction "CLR_1") (pintype "input"))
      (node (ref "E4") (pin "13") (pinfunction "CLR_13") (pintype "input"))
      (node (ref "E8") (pin "13") (pinfunction "CLR_13") (pintype "input"))
    )
    (net (code "176") (name "RX_RATE") (class "Default")
      (node (ref "E18") (pin "1") (pinfunction "CKB_1") (pintype "input"))
      (node (ref "E18") (pin "12") (pinfunction "QA_12") (pintype "output"))
      (node (ref "E19") (pin "13") (pinfunction "I2_13") (pintype "input"))
      (node (ref "E3") (pin "10") (pinfunction "PRE_10") (pintype "input"))
      (node (ref "E3") (pin "3") (pinfunction "CLK_3") (pintype "input"))
      (node (ref "H123") (pin "3") (pinfunction "3_3") (pintype "passive"))
    )
    (net (code "177") (name "RX_SEL_L") (class "Default")
      (node (ref "E42") (pin "12") (pinfunction "O_12") (pintype "output"))
      (node (ref "E43") (pin "2") (pinfunction "D_2") (pintype "input"))
    )
    (net (code "178") (name "SELECTED_L") (class "Default")
      (node (ref "E23") (pin "3") (pinfunction "O_3") (pintype "output"))
      (node (ref "E46") (pin "10") (pinfunction "I1_10") (pintype "input"))
      (node (ref "E46") (pin "5") (pinfunction "I1_5") (pintype "input"))
      (node (ref "E46") (pin "6") (pinfunction "I0_6") (pintype "input"))
    )
    (net (code "179") (name "SERIAL_IN") (class "Default")
      (node (ref "E11") (pin "3") (pinfunction "I1_3") (pintype "input"))
      (node (ref "E19") (pin "1") (pinfunction "I0_1") (pintype "input"))
      (node (ref "E21") (pin "9") (pinfunction "I_9") (pintype "input"))
      (node (ref "J1") (pin "E") (pinfunction "5_E") (pintype "bidirectional"))
    )
    (net (code "180") (name "SKIP_L") (class "Default")
      (node (ref "E37") (pin "10") (pinfunction "O_10") (pintype "open_collector"))
      (node (ref "U$2") (pin "CS1") (pinfunction "1_CS1") (pintype "bidirectional"))
    )
    (net (code "181") (name "STP_MARK") (class "Default")
      (node (ref "E25") (pin "1") (pinfunction "I4_1") (pintype "input"))
      (node (ref "J23") (pin "2") (pinfunction "2_2") (pintype "passive"))
      (node (ref "JJ23") (pin "2") (pinfunction "2_2") (pintype "passive"))
    )
    (net (code "182") (name "TKSKP") (class "Default")
      (node (ref "E39") (pin "4") (pinfunction "I3_4") (pintype "input"))
      (node (ref "E39") (pin "5") (pinfunction "I4_5") (pintype "input"))
      (node (ref "E42") (pin "10") (pinfunction "O_10") (pintype "output"))
    )
    (net (code "183") (name "TP3") (class "Default")
      (node (ref "E34") (pin "9") (pinfunction "I0_9") (pintype "input"))
      (node (ref "U$2") (pin "CH2") (pinfunction "1_CH2") (pintype "bidirectional"))
    )
    (net (code "184") (name "TSKP") (class "Default")
      (node (ref "E45") (pin "13") (pinfunction "O_13") (pintype "output"))
      (node (ref "E45") (pin "6") (pinfunction "I1_6") (pintype "input"))
    )
    (net (code "185") (name "TX7") (class "Default")
      (node (ref "E19") (pin "8") (pinfunction "O_8") (pintype "output"))
      (node (ref "E38") (pin "2") (pinfunction "D_2") (pintype "input"))
    )
    (net (code "186") (name "TX8") (class "Default")
      (node (ref "E19") (pin "6") (pinfunction "O_6") (pintype "output"))
      (node (ref "E25") (pin "10") (pinfunction "I1_10") (pintype "input"))
    )
    (net (code "187") (name "TX_20MA+") (class "Default")
      (node (ref "D6") (pin "C") (pinfunction "C_C") (pintype "passive"))
      (node (ref "D9") (pin "C") (pinfunction "C_C") (pintype "passive"))
      (node (ref "J1") (pin "AA") (pinfunction "23_AA") (pintype "bidirectional"))
      (node (ref "R25") (pin "2") (pinfunction "2_2") (pintype "passive"))
    )
    (net (code "188") (name "TX_20MA-") (class "Default")
      (node (ref "J1") (pin "KK") (pinfunction "31_KK") (pintype "bidirectional"))
      (node (ref "R11") (pin "2") (pinfunction "2_2") (pintype "passive"))
    )
    (net (code "189") (name "TX_ACTIVE") (class "Default")
      (node (ref "E20") (pin "11") (pinfunction "CLK_11") (pintype "input"))
      (node (ref "E20") (pin "6") (pinfunction "~{Q}_6") (pintype "output"))
      (node (ref "E25") (pin "9") (pinfunction "I2_9") (pintype "input"))
      (node (ref "E29") (pin "4") (pinfunction "PRE_4") (pintype "input"))
      (node (ref "E35") (pin "10") (pinfunction "I1_10") (pintype "input"))
      (node (ref "U$2") (pin "BA1") (pinfunction "1_BA1") (pintype "bidirectional"))
    )
    (net (code "190") (name "TX_DATA") (class "Default")
      (node (ref "E29") (pin "2") (pinfunction "D_2") (pintype "input"))
      (node (ref "E31") (pin "11") (pinfunction "Q3_11") (pintype "output"))
    )
    (net (code "191") (name "TX_DIV") (class "Default")
      (node (ref "E16") (pin "5") (pinfunction "Q_5") (pintype "output"))
      (node (ref "E25") (pin "4") (pinfunction "I3_4") (pintype "input"))
      (node (ref "E26") (pin "1") (pinfunction "R_1") (pintype "input"))
      (node (ref "E29") (pin "3") (pinfunction "CLK_3") (pintype "input"))
      (node (ref "E35") (pin "9") (pinfunction "I0_9") (pintype "input"))
      (node (ref "E38") (pin "3") (pinfunction "CLK_3") (pintype "input"))
    )
    (net (code "192") (name "TX_RATE") (class "Default")
      (node (ref "E16") (pin "3") (pinfunction "CLK_3") (pintype "input"))
      (node (ref "E20") (pin "13") (pinfunction "CLR_13") (pintype "input"))
      (node (ref "E20") (pin "3") (pinfunction "CLK_3") (pintype "input"))
      (node (ref "E21") (pin "5") (pinfunction "I_5") (pintype "input"))
      (node (ref "H12") (pin "2") (pinfunction "2_2") (pintype "passive"))
      (node (ref "H123") (pin "2") (pinfunction "2_2") (pintype "passive"))
    )
    (net (code "193") (name "TX_SEL_L") (class "Default")
      (node (ref "E33") (pin "10") (pinfunction "O_10") (pintype "open_collector"))
      (node (ref "E40") (pin "2") (pinfunction "D_2") (pintype "input"))
      (node (ref "R26") (pin "1") (pinfunction "1_1") (pintype "passive"))
    )
    (net (code "194") (name "VCC") (class "Default")
      (node (ref "C1") (pin "1") (pinfunction "1_1") (pintype "passive"))
      (node (ref "C10") (pin "1") (pinfunction "1_1") (pintype "passive"))
      (node (ref "C11") (pin "1") (pinfunction "1_1") (pintype "passive"))
      (node (ref "C12") (pin "1") (pinfunction "1_1") (pintype "passive"))
      (node (ref "C13") (pin "1") (pinfunction "1_1") (pintype "passive"))
      (node (ref "C14") (pin "1") (pinfunction "1_1") (pintype "passive"))
      (node (ref "C15") (pin "1") (pinfunction "1_1") (pintype "passive"))
      (node (ref "C16") (pin "1") (pinfunction "1_1") (pintype "passive"))
      (node (ref "C17") (pin "1") (pinfunction "1_1") (pintype "passive"))
      (node (ref "C18") (pin "1") (pinfunction "1_1") (pintype "passive"))
      (node (ref "C19") (pin "1") (pinfunction "1_1") (pintype "passive"))
      (node (ref "C2") (pin "1") (pinfunction "1_1") (pintype "passive"))
      (node (ref "C20") (pin "1") (pinfunction "1_1") (pintype "passive"))
      (node (ref "C21") (pin "1") (pinfunction "1_1") (pintype "passive"))
      (node (ref "C22") (pin "1") (pinfunction "1_1") (pintype "passive"))
      (node (ref "C23") (pin "1") (pinfunction "1_1") (pintype "passive"))
      (node (ref "C24") (pin "1") (pinfunction "1_1") (pintype "passive"))
      (node (ref "C25") (pin "1") (pinfunction "1_1") (pintype "passive"))
      (node (ref "C26") (pin "1") (pinfunction "1_1") (pintype "passive"))
      (node (ref "C27") (pin "1") (pinfunction "1_1") (pintype "passive"))
      (node (ref "C28") (pin "1") (pinfunction "1_1") (pintype "passive"))
      (node (ref "C29") (pin "1") (pinfunction "1_1") (pintype "passive"))
      (node (ref "C3") (pin "1") (pinfunction "1_1") (pintype "passive"))
      (node (ref "C30") (pin "1") (pinfunction "1_1") (pintype "passive"))
      (node (ref "C31") (pin "1") (pinfunction "1_1") (pintype "passive"))
      (node (ref "C33") (pin "1") (pinfunction "1_1") (pintype "passive"))
      (node (ref "C34") (pin "1") (pinfunction "1_1") (pintype "passive"))
      (node (ref "C35") (pin "1") (pinfunction "1_1") (pintype "passive"))
      (node (ref "C36") (pin "1") (pinfunction "1_1") (pintype "passive"))
      (node (ref "C37") (pin "1") (pinfunction "1_1") (pintype "passive"))
      (node (ref "C38") (pin "1") (pinfunction "1_1") (pintype "passive"))
      (node (ref "C39") (pin "1") (pinfunction "1_1") (pintype "passive"))
      (node (ref "C4") (pin "1") (pinfunction "1_1") (pintype "passive"))
      (node (ref "C40") (pin "1") (pinfunction "1_1") (pintype "passive"))
      (node (ref "C41") (pin "1") (pinfunction "1_1") (pintype "passive"))
      (node (ref "C42") (pin "1") (pinfunction "1_1") (pintype "passive"))
      (node (ref "C43") (pin "1") (pinfunction "1_1") (pintype "passive"))
      (node (ref "C44") (pin "1") (pinfunction "1_1") (pintype "passive"))
      (node (ref "C45") (pin "1") (pinfunction "1_1") (pintype "passive"))
      (node (ref "C46") (pin "1") (pinfunction "1_1") (pintype "passive"))
      (node (ref "C47") (pin "1") (pinfunction "1_1") (pintype "passive"))
      (node (ref "C48") (pin "1") (pinfunction "1_1") (pintype "passive"))
      (node (ref "C5") (pin "1") (pinfunction "1_1") (pintype "passive"))
      (node (ref "C51") (pin "+") (pinfunction "+_+") (pintype "passive"))
      (node (ref "C52") (pin "+") (pinfunction "+_+") (pintype "passive"))
      (node (ref "C53") (pin "+") (pinfunction "+_+") (pintype "passive"))
      (node (ref "C56") (pin "+") (pinfunction "+_+") (pintype "passive"))
      (node (ref "C57") (pin "1") (pinfunction "1_1") (pintype "passive"))
      (node (ref "C6") (pin "1") (pinfunction "1_1") (pintype "passive"))
      (node (ref "C7") (pin "1") (pinfunction "1_1") (pintype "passive"))
      (node (ref "C8") (pin "1") (pinfunction "1_1") (pintype "passive"))
      (node (ref "C9") (pin "1") (pinfunction "1_1") (pintype "passive"))
      (node (ref "D7") (pin "C") (pinfunction "C_C") (pintype "passive"))
      (node (ref "Q1") (pin "3") (pinfunction "C_3") (pintype "passive"))
      (node (ref "Q3") (pin "1") (pinfunction "E_1") (pintype "passive"))
      (node (ref "R1") (pin "2") (pinfunction "2_2") (pintype "passive"))
      (node (ref "R10") (pin "2") (pinfunction "2_2") (pintype "passive"))
      (node (ref "R14") (pin "2") (pinfunction "2_2") (pintype "passive"))
      (node (ref "R15") (pin "2") (pinfunction "2_2") (pintype "passive"))
      (node (ref "R16") (pin "2") (pinfunction "2_2") (pintype "passive"))
      (node (ref "R21") (pin "2") (pinfunction "2_2") (pintype "passive"))
      (node (ref "R24") (pin "2") (pinfunction "2_2") (pintype "passive"))
      (node (ref "R26") (pin "2") (pinfunction "2_2") (pintype "passive"))
      (node (ref "R3") (pin "2") (pinfunction "2_2") (pintype "passive"))
      (node (ref "R7") (pin "2") (pinfunction "2_2") (pintype "passive"))
      (node (ref "R8") (pin "2") (pinfunction "2_2") (pintype "passive"))
      (node (ref "U$2") (pin "AA2") (pinfunction "1_AA2") (pintype "bidirectional"))
      (node (ref "U$2") (pin "BA2") (pinfunction "1_BA2") (pintype "bidirectional"))
      (node (ref "U$2") (pin "CA2") (pinfunction "1_CA2") (pintype "bidirectional"))
    )
    (net (code "195") (name "unconnected-(E3B-Q-Pad9)") (class "Default")
      (node (ref "E3") (pin "9") (pinfunction "Q_9") (pintype "output"))
    )
    (net (code "196") (name "unconnected-(E4A-Q-Pad5)") (class "Default")
      (node (ref "E4") (pin "5") (pinfunction "Q_5") (pintype "output"))
    )
    (net (code "197") (name "unconnected-(E4B-Q-Pad9)") (class "Default")
      (node (ref "E4") (pin "9") (pinfunction "Q_9") (pintype "output"))
    )
    (net (code "198") (name "unconnected-(E5A-QB-Pad9)") (class "Default")
      (node (ref "E5") (pin "9") (pinfunction "QB_9") (pintype "output"))
    )
    (net (code "199") (name "unconnected-(E5A-QC-Pad8)") (class "Default")
      (node (ref "E5") (pin "8") (pinfunction "QC_8") (pintype "output"))
    )
    (net (code "200") (name "unconnected-(E6A-Q4-Pad12)") (class "Default")
      (node (ref "E6") (pin "12") (pinfunction "Q4_12") (pintype "output"))
    )
    (net (code "201") (name "unconnected-(E7B-~{Q}-Pad8)") (class "Default")
      (node (ref "E7") (pin "8") (pinfunction "~{Q}_8") (pintype "output"))
    )
    (net (code "202") (name "unconnected-(E16B-Q-Pad9)") (class "Default")
      (node (ref "E16") (pin "9") (pinfunction "Q_9") (pintype "output"))
    )
    (net (code "203") (name "unconnected-(E18A-QB-Pad9)") (class "Default")
      (node (ref "E18") (pin "9") (pinfunction "QB_9") (pintype "output"))
    )
    (net (code "204") (name "unconnected-(E18A-QC-Pad8)") (class "Default")
      (node (ref "E18") (pin "8") (pinfunction "QC_8") (pintype "output"))
    )
    (net (code "205") (name "unconnected-(E20B-Q-Pad9)") (class "Default")
      (node (ref "E20") (pin "9") (pinfunction "Q_9") (pintype "output"))
    )
    (net (code "206") (name "unconnected-(E22A-BO-Pad13)") (class "Default")
      (node (ref "E22") (pin "13") (pinfunction "BO_13") (pintype "output"))
    )
    (net (code "207") (name "unconnected-(E22A-CO-Pad12)") (class "Default")
      (node (ref "E22") (pin "12") (pinfunction "CO_12") (pintype "output"))
    )
    (net (code "208") (name "unconnected-(E22A-QA-Pad3)") (class "Default")
      (node (ref "E22") (pin "3") (pinfunction "QA_3") (pintype "output"))
    )
    (net (code "209") (name "unconnected-(E22A-QB-Pad2)") (class "Default")
      (node (ref "E22") (pin "2") (pinfunction "QB_2") (pintype "output"))
    )
    (net (code "210") (name "unconnected-(E22A-QC-Pad6)") (class "Default")
      (node (ref "E22") (pin "6") (pinfunction "QC_6") (pintype "output"))
    )
    (net (code "211") (name "unconnected-(E25A-I5-Pad12)") (class "Default")
      (node (ref "E25") (pin "12") (pinfunction "I5_12") (pintype "passive"))
    )
    (net (code "212") (name "unconnected-(E25A-I6-Pad11)") (class "Default")
      (node (ref "E25") (pin "11") (pinfunction "I6_11") (pintype "passive"))
    )
    (net (code "213") (name "unconnected-(E26A-I0-Pad3)") (class "Default")
      (node (ref "E26") (pin "3") (pinfunction "I0_3") (pintype "input"))
    )
    (net (code "214") (name "unconnected-(E26A-I1-Pad2)") (class "Default")
      (node (ref "E26") (pin "2") (pinfunction "I1_2") (pintype "input"))
    )
    (net (code "215") (name "unconnected-(E26A-I2-Pad15)") (class "Default")
      (node (ref "E26") (pin "15") (pinfunction "I2_15") (pintype "input"))
    )
    (net (code "216") (name "unconnected-(E26A-I3-Pad14)") (class "Default")
      (node (ref "E26") (pin "14") (pinfunction "I3_14") (pintype "input"))
    )
    (net (code "217") (name "unconnected-(E26A-Q1-Pad7)") (class "Default")
      (node (ref "E26") (pin "7") (pinfunction "Q1_7") (pintype "output"))
    )
    (net (code "218") (name "unconnected-(E26A-Q3-Pad11)") (class "Default")
      (node (ref "E26") (pin "11") (pinfunction "Q3_11") (pintype "output"))
    )
    (net (code "219") (name "unconnected-(E26A-Q4-Pad12)") (class "Default")
      (node (ref "E26") (pin "12") (pinfunction "Q4_12") (pintype "output"))
    )
    (net (code "220") (name "unconnected-(E28A-Q4-Pad12)") (class "Default")
      (node (ref "E28") (pin "12") (pinfunction "Q4_12") (pintype "output"))
    )
    (net (code "221") (name "unconnected-(E29B-~{Q}-Pad8)") (class "Default")
      (node (ref "E29") (pin "8") (pinfunction "~{Q}_8") (pintype "output"))
    )
    (net (code "222") (name "unconnected-(E31A-Q4-Pad12)") (class "Default")
      (node (ref "E31") (pin "12") (pinfunction "Q4_12") (pintype "output"))
    )
    (net (code "223") (name "unconnected-(E38A-~{Q}-Pad6)") (class "Default")
      (node (ref "E38") (pin "6") (pinfunction "~{Q}_6") (pintype "output"))
    )
    (net (code "224") (name "unconnected-(E39A-I5-Pad12)") (class "Default")
      (node (ref "E39") (pin "12") (pinfunction "I5_12") (pintype "passive"))
    )
    (net (code "225") (name "unconnected-(E39A-I6-Pad11)") (class "Default")
      (node (ref "E39") (pin "11") (pinfunction "I6_11") (pintype "passive"))
    )
    (net (code "226") (name "unconnected-(E40A-3-Pad10)") (class "Default")
      (node (ref "E40") (pin "10") (pinfunction "3_10") (pintype "output"))
    )
    (net (code "227") (name "unconnected-(E40A-7-Pad5)") (class "Default")
      (node (ref "E40") (pin "5") (pinfunction "7_5") (pintype "output"))
    )
    (net (code "228") (name "unconnected-(E40A-8-Pad6)") (class "Default")
      (node (ref "E40") (pin "6") (pinfunction "8_6") (pintype "output"))
    )
    (net (code "229") (name "unconnected-(E40A-9-Pad7)") (class "Default")
      (node (ref "E40") (pin "7") (pinfunction "9_7") (pintype "output"))
    )
    (net (code "230") (name "unconnected-(E43A-3-Pad10)") (class "Default")
      (node (ref "E43") (pin "10") (pinfunction "3_10") (pintype "output"))
    )
    (net (code "231") (name "unconnected-(E43A-7-Pad5)") (class "Default")
      (node (ref "E43") (pin "5") (pinfunction "7_5") (pintype "output"))
    )
    (net (code "232") (name "unconnected-(E43A-8-Pad6)") (class "Default")
      (node (ref "E43") (pin "6") (pinfunction "8_6") (pintype "output"))
    )
    (net (code "233") (name "unconnected-(E43A-9-Pad7)") (class "Default")
      (node (ref "E43") (pin "7") (pinfunction "9_7") (pintype "output"))
    )
    (net (code "234") (name "unconnected-(E48A-Q-Pad5)") (class "Default")
      (node (ref "E48") (pin "5") (pinfunction "Q_5") (pintype "output"))
    )
    (net (code "235") (name "unconnected-(E48B-~{Q}-Pad8)") (class "Default")
      (node (ref "E48") (pin "8") (pinfunction "~{Q}_8") (pintype "output"))
    )
    (net (code "236") (name "unconnected-(J1-4-PadD)") (class "Default")
      (node (ref "J1") (pin "D") (pinfunction "4_D") (pintype "bidirectional"))
    )
    (net (code "237") (name "unconnected-(J1-10-PadL)") (class "Default")
      (node (ref "J1") (pin "L") (pinfunction "10_L") (pintype "bidirectional"))
    )
    (net (code "238") (name "unconnected-(J1-12-PadN)") (class "Default")
      (node (ref "J1") (pin "N") (pinfunction "12_N") (pintype "bidirectional"))
    )
    (net (code "239") (name "unconnected-(J1-13-PadP)") (class "Default")
      (node (ref "J1") (pin "P") (pinfunction "13_P") (pintype "bidirectional"))
    )
    (net (code "240") (name "unconnected-(J1-14-PadR)") (class "Default")
      (node (ref "J1") (pin "R") (pinfunction "14_R") (pintype "bidirectional"))
    )
    (net (code "241") (name "unconnected-(J1-16-PadT)") (class "Default")
      (node (ref "J1") (pin "T") (pinfunction "16_T") (pintype "bidirectional"))
    )
    (net (code "242") (name "unconnected-(J1-17-PadU)") (class "Default")
      (node (ref "J1") (pin "U") (pinfunction "17_U") (pintype "bidirectional"))
    )
    (net (code "243") (name "unconnected-(J1-19-PadW)") (class "Default")
      (node (ref "J1") (pin "W") (pinfunction "19_W") (pintype "bidirectional"))
    )
    (net (code "244") (name "unconnected-(J1-20-PadX)") (class "Default")
      (node (ref "J1") (pin "X") (pinfunction "20_X") (pintype "bidirectional"))
    )
    (net (code "245") (name "unconnected-(J1-21-PadY)") (class "Default")
      (node (ref "J1") (pin "Y") (pinfunction "21_Y") (pintype "bidirectional"))
    )
    (net (code "246") (name "unconnected-(J1-22-PadZ)") (class "Default")
      (node (ref "J1") (pin "Z") (pinfunction "22_Z") (pintype "bidirectional"))
    )
    (net (code "247") (name "unconnected-(J1-24-PadBB)") (class "Default")
      (node (ref "J1") (pin "BB") (pinfunction "24_BB") (pintype "bidirectional"))
    )
    (net (code "248") (name "unconnected-(J1-25-PadCC)") (class "Default")
      (node (ref "J1") (pin "CC") (pinfunction "25_CC") (pintype "bidirectional"))
    )
    (net (code "249") (name "unconnected-(J1-28-PadFF)") (class "Default")
      (node (ref "J1") (pin "FF") (pinfunction "28_FF") (pintype "bidirectional"))
    )
    (net (code "250") (name "unconnected-(J1-29-PadHH)") (class "Default")
      (node (ref "J1") (pin "HH") (pinfunction "29_HH") (pintype "bidirectional"))
    )
    (net (code "251") (name "unconnected-(J1-30-PadJJ)") (class "Default")
      (node (ref "J1") (pin "JJ") (pinfunction "30_JJ") (pintype "bidirectional"))
    )
    (net (code "252") (name "unconnected-(J1-32-PadLL)") (class "Default")
      (node (ref "J1") (pin "LL") (pinfunction "32_LL") (pintype "bidirectional"))
    )
    (net (code "253") (name "unconnected-(J1-33-PadMM)") (class "Default")
      (node (ref "J1") (pin "MM") (pinfunction "33_MM") (pintype "bidirectional"))
    )
    (net (code "254") (name "unconnected-(J1-34-PadNN)") (class "Default")
      (node (ref "J1") (pin "NN") (pinfunction "34_NN") (pintype "bidirectional"))
    )
    (net (code "255") (name "unconnected-(J1-36-PadRR)") (class "Default")
      (node (ref "J1") (pin "RR") (pinfunction "36_RR") (pintype "bidirectional"))
    )
    (net (code "256") (name "unconnected-(J1-37-PadSS)") (class "Default")
      (node (ref "J1") (pin "SS") (pinfunction "37_SS") (pintype "bidirectional"))
    )
    (net (code "257") (name "unconnected-(J1-38-PadTT)") (class "Default")
      (node (ref "J1") (pin "TT") (pinfunction "38_TT") (pintype "bidirectional"))
    )
    (net (code "258") (name "~{CKKCC}") (class "Default")
      (node (ref "E35") (pin "4") (pinfunction "I0_4") (pintype "input"))
      (node (ref "E44") (pin "11") (pinfunction "O_11") (pintype "output"))
      (node (ref "E48") (pin "13") (pinfunction "CLR_13") (pintype "input"))
    )
    (net (code "259") (name "~{CKTFL}") (class "Default")
      (node (ref "E38") (pin "1") (pinfunction "CLR_1") (pintype "input"))
      (node (ref "E42") (pin "2") (pinfunction "O_2") (pintype "output"))
    )
    (net (code "260") (name "~{DOTPC}") (class "Default")
      (node (ref "E27") (pin "10") (pinfunction "I1_10") (pintype "input"))
      (node (ref "E27") (pin "11") (pinfunction "I0_11") (pintype "input"))
      (node (ref "E27") (pin "5") (pinfunction "I1_5") (pintype "input"))
      (node (ref "E27") (pin "6") (pinfunction "I0_6") (pintype "input"))
      (node (ref "E28") (pin "13") (pinfunction "S_13") (pintype "input"))
      (node (ref "E30") (pin "10") (pinfunction "I1_10") (pintype "input"))
      (node (ref "E30") (pin "11") (pinfunction "I0_11") (pintype "input"))
      (node (ref "E30") (pin "5") (pinfunction "I1_5") (pintype "input"))
      (node (ref "E30") (pin "6") (pinfunction "I0_6") (pintype "input"))
      (node (ref "E31") (pin "13") (pinfunction "S_13") (pintype "input"))
      (node (ref "E35") (pin "3") (pinfunction "O_3") (pintype "output"))
      (node (ref "R10") (pin "1") (pinfunction "1_1") (pintype "passive"))
    )
    (net (code "261") (name "~{INIT}") (class "Default")
      (node (ref "E16") (pin "13") (pinfunction "CLR_13") (pintype "input"))
      (node (ref "E16") (pin "4") (pinfunction "PRE_4") (pintype "input"))
      (node (ref "E29") (pin "13") (pinfunction "CLR_13") (pintype "input"))
      (node (ref "E46") (pin "13") (pinfunction "O_13") (pintype "output"))
      (node (ref "E48") (pin "10") (pinfunction "PRE_10") (pintype "input"))
    )
    (net (code "262") (name "~{INT_ENAB}") (class "Default")
      (node (ref "E38") (pin "9") (pinfunction "Q_9") (pintype "output"))
      (node (ref "E45") (pin "9") (pinfunction "I1_9") (pintype "input"))
    )
    (net (code "263") (name "~{KCC}") (class "Default")
      (node (ref "E43") (pin "11") (pinfunction "2_11") (pintype "output"))
      (node (ref "E44") (pin "10") (pinfunction "I1_10") (pintype "input"))
    )
    (net (code "264") (name "~{KCF}") (class "Default")
      (node (ref "E43") (pin "13") (pinfunction "0_13") (pintype "output"))
      (node (ref "E47") (pin "6") (pinfunction "I1_6") (pintype "input"))
    )
    (net (code "265") (name "~{KIE}") (class "Default")
      (node (ref "E43") (pin "3") (pinfunction "5_3") (pintype "output"))
      (node (ref "E47") (pin "8") (pinfunction "I0_8") (pintype "input"))
    )
    (net (code "266") (name "~{KRB}") (class "Default")
      (node (ref "E43") (pin "4") (pinfunction "6_4") (pintype "output"))
      (node (ref "E44") (pin "4") (pinfunction "I0_4") (pintype "input"))
      (node (ref "E44") (pin "9") (pinfunction "I0_9") (pintype "input"))
    )
    (net (code "267") (name "~{KRS}") (class "Default")
      (node (ref "E43") (pin "9") (pinfunction "4_9") (pintype "output"))
      (node (ref "E44") (pin "5") (pinfunction "I1_5") (pintype "input"))
    )
    (net (code "268") (name "~{KSF}") (class "Default")
      (node (ref "E43") (pin "12") (pinfunction "1_12") (pintype "output"))
      (node (ref "E47") (pin "11") (pinfunction "I0_11") (pintype "input"))
    )
    (net (code "269") (name "~{LAST_UNIT}") (class "Default")
      (node (ref "E12") (pin "12") (pinfunction "I0_12") (pintype "input"))
      (node (ref "E8") (pin "6") (pinfunction "~{Q}_6") (pintype "output"))
    )
    (net (code "270") (name "~{LINE}") (class "Default")
      (node (ref "E29") (pin "6") (pinfunction "~{Q}_6") (pintype "output"))
      (node (ref "R13") (pin "1") (pinfunction "1_1") (pintype "passive"))
      (node (ref "R14") (pin "1") (pinfunction "1_1") (pintype "passive"))
    )
    (net (code "271") (name "~{P_PULSE}") (class "Default")
      (node (ref "E10") (pin "13") (pinfunction "S_13") (pintype "input"))
      (node (ref "E11") (pin "8") (pinfunction "I0_8") (pintype "input"))
      (node (ref "E6") (pin "13") (pinfunction "S_13") (pintype "input"))
      (node (ref "E7") (pin "9") (pinfunction "Q_9") (pintype "output"))
    )
    (net (code "272") (name "~{RFLG}") (class "Default")
      (node (ref "E44") (pin "1") (pinfunction "I0_1") (pintype "input"))
      (node (ref "E47") (pin "12") (pinfunction "I1_12") (pintype "input"))
      (node (ref "E48") (pin "6") (pinfunction "~{Q}_6") (pintype "output"))
    )
    (net (code "273") (name "~{RX_ACTIVE8}") (class "Default")
      (node (ref "E11") (pin "11") (pinfunction "I0_11") (pintype "input"))
      (node (ref "E11") (pin "12") (pinfunction "I1_12") (pintype "input"))
      (node (ref "E12") (pin "3") (pinfunction "O_3") (pintype "output"))
      (node (ref "E16") (pin "11") (pinfunction "CLK_11") (pintype "input"))
      (node (ref "E39") (pin "1") (pinfunction "I4_1") (pintype "input"))
    )
    (net (code "274") (name "~{RX_ACTIVE}") (class "Default")
      (node (ref "E12") (pin "13") (pinfunction "I1_13") (pintype "input"))
      (node (ref "E12") (pin "4") (pinfunction "I0_4") (pintype "input"))
      (node (ref "E7") (pin "6") (pinfunction "~{Q}_6") (pintype "output"))
    )
    (net (code "275") (name "~{RX_AGAIN}") (class "Default")
      (node (ref "E16") (pin "10") (pinfunction "PRE_10") (pintype "input"))
      (node (ref "E19") (pin "12") (pinfunction "O_12") (pintype "output"))
      (node (ref "E7") (pin "4") (pinfunction "PRE_4") (pintype "input"))
    )
    (net (code "276") (name "~{RX_DIV2}") (class "Default")
      (node (ref "E11") (pin "9") (pinfunction "I1_9") (pintype "input"))
      (node (ref "E4") (pin "11") (pinfunction "CLK_11") (pintype "input"))
      (node (ref "E4") (pin "2") (pinfunction "D_2") (pintype "input"))
      (node (ref "E4") (pin "6") (pinfunction "~{Q}_6") (pintype "output"))
    )
    (net (code "277") (name "~{RX_DIV4}") (class "Default")
      (node (ref "E4") (pin "12") (pinfunction "D_12") (pintype "input"))
      (node (ref "E4") (pin "8") (pinfunction "~{Q}_8") (pintype "output"))
      (node (ref "E7") (pin "10") (pinfunction "PRE_10") (pintype "input"))
      (node (ref "E8") (pin "11") (pinfunction "CLK_11") (pintype "input"))
    )
    (net (code "278") (name "~{RX_DIV}") (class "Default")
      (node (ref "E3") (pin "6") (pinfunction "~{Q}_6") (pintype "output"))
      (node (ref "E4") (pin "3") (pinfunction "CLK_3") (pintype "input"))
    )
    (net (code "279") (name "~{RX_LAST}") (class "Default")
      (node (ref "E12") (pin "10") (pinfunction "I1_10") (pintype "input"))
      (node (ref "E12") (pin "11") (pinfunction "O_11") (pintype "output"))
      (node (ref "E21") (pin "11") (pinfunction "I_11") (pintype "input"))
      (node (ref "E36") (pin "4") (pinfunction "I0_4") (pintype "input"))
      (node (ref "E36") (pin "5") (pinfunction "I1_5") (pintype "input"))
      (node (ref "R15") (pin "1") (pinfunction "1_1") (pintype "passive"))
    )
    (net (code "280") (name "~{R_RUN}") (class "Default")
      (node (ref "E48") (pin "9") (pinfunction "Q_9") (pintype "output"))
      (node (ref "Q2") (pin "2") (pinfunction "B_2") (pintype "passive"))
      (node (ref "U$2") (pin "DB1") (pinfunction "1_DB1") (pintype "bidirectional"))
    )
    (net (code "281") (name "~{SPIKE_DET}") (class "Default")
      (node (ref "E11") (pin "2") (pinfunction "I0_2") (pintype "input"))
      (node (ref "E16") (pin "8") (pinfunction "~{Q}_8") (pintype "output"))
    )
    (net (code "282") (name "~{START}") (class "Default")
      (node (ref "E20") (pin "8") (pinfunction "~{Q}_8") (pintype "output"))
      (node (ref "E29") (pin "1") (pinfunction "CLR_1") (pintype "input"))
    )
    (net (code "283") (name "~{TCF}") (class "Default")
      (node (ref "E40") (pin "11") (pinfunction "2_11") (pintype "output"))
      (node (ref "E41") (pin "10") (pinfunction "I1_10") (pintype "input"))
    )
    (net (code "284") (name "~{TFLG}") (class "Default")
      (node (ref "E38") (pin "5") (pinfunction "Q_5") (pintype "output"))
      (node (ref "E44") (pin "2") (pinfunction "I1_2") (pintype "input"))
      (node (ref "E45") (pin "11") (pinfunction "I0_11") (pintype "input"))
    )
    (net (code "285") (name "~{TFL}") (class "Default")
      (node (ref "E40") (pin "13") (pinfunction "0_13") (pintype "output"))
      (node (ref "E45") (pin "2") (pinfunction "I0_2") (pintype "input"))
    )
    (net (code "286") (name "~{TLS}") (class "Default")
      (node (ref "E40") (pin "4") (pinfunction "6_4") (pintype "output"))
      (node (ref "E41") (pin "4") (pinfunction "I0_4") (pintype "input"))
      (node (ref "E41") (pin "9") (pinfunction "I0_9") (pintype "input"))
    )
    (net (code "287") (name "~{TP3}") (class "Default")
      (node (ref "E25") (pin "2") (pinfunction "I1_2") (pintype "input"))
      (node (ref "E34") (pin "14") (pinfunction "O_14") (pintype "output"))
      (node (ref "E41") (pin "13") (pinfunction "I1_13") (pintype "input"))
      (node (ref "E42") (pin "3") (pinfunction "I_3") (pintype "input"))
      (node (ref "E44") (pin "13") (pinfunction "I1_13") (pintype "input"))
    )
    (net (code "288") (name "~{TPC}") (class "Default")
      (node (ref "E40") (pin "9") (pinfunction "4_9") (pintype "output"))
      (node (ref "E41") (pin "5") (pinfunction "I1_5") (pintype "input"))
    )
    (net (code "289") (name "~{TSF}") (class "Default")
      (node (ref "E40") (pin "12") (pinfunction "1_12") (pintype "output"))
      (node (ref "E45") (pin "12") (pinfunction "I1_12") (pintype "input"))
    )
    (net (code "290") (name "~{TSK}") (class "Default")
      (node (ref "E40") (pin "3") (pinfunction "5_3") (pintype "output"))
      (node (ref "E45") (pin "8") (pinfunction "I0_8") (pintype "input"))
    )
    (net (code "291") (name "~{TX_ACTIVE}") (class "Default")
      (node (ref "E20") (pin "5") (pinfunction "Q_5") (pintype "output"))
      (node (ref "E26") (pin "4") (pinfunction "D_4") (pintype "input"))
    )
    (net (code "292") (name "~{TX_DIV}") (class "Default")
      (node (ref "DL1") (pin "1") (pinfunction "1_1") (pintype "passive"))
      (node (ref "E16") (pin "6") (pinfunction "~{Q}_6") (pintype "output"))
      (node (ref "E19") (pin "4") (pinfunction "I1_4") (pintype "input"))
      (node (ref "R21") (pin "1") (pinfunction "1_1") (pintype "passive"))
    )
    (net (code "293") (name "~{TX_SHIFT}") (class "Default")
      (node (ref "E21") (pin "3") (pinfunction "I_3") (pintype "input"))
      (node (ref "E25") (pin "6") (pinfunction "O_6") (pintype "output"))
      (node (ref "E28") (pin "6") (pinfunction "C_6") (pintype "input"))
      (node (ref "E31") (pin "6") (pinfunction "C_6") (pintype "input"))
    )
  )
)
